# 612_jetracer_esp32s3_030007.net
KiCad netlist of a schematic drawn in EAGLE
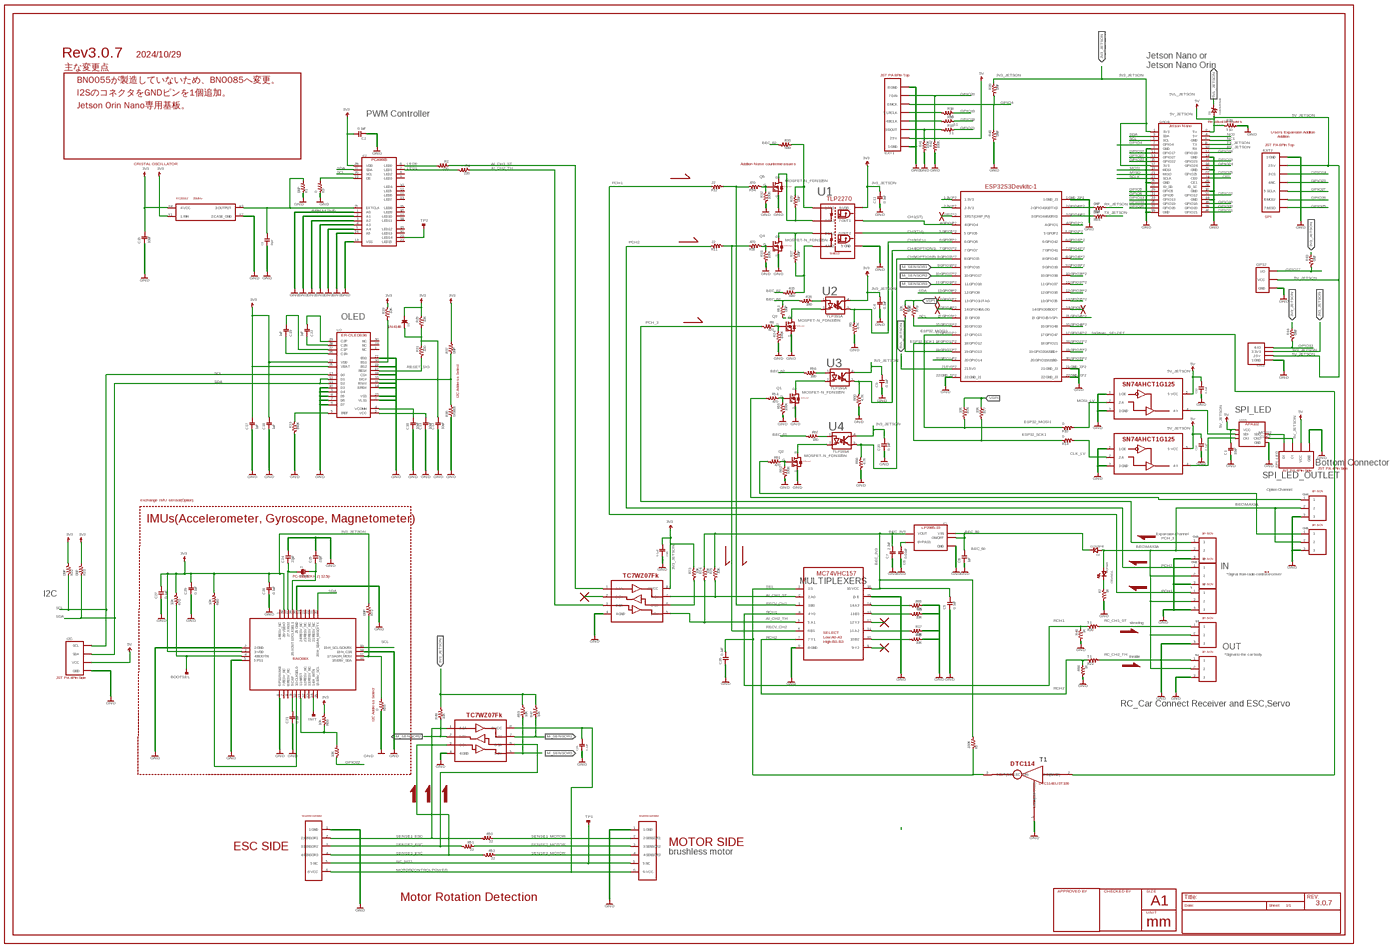
[diagram p0: schematic, sheet 1, overview]
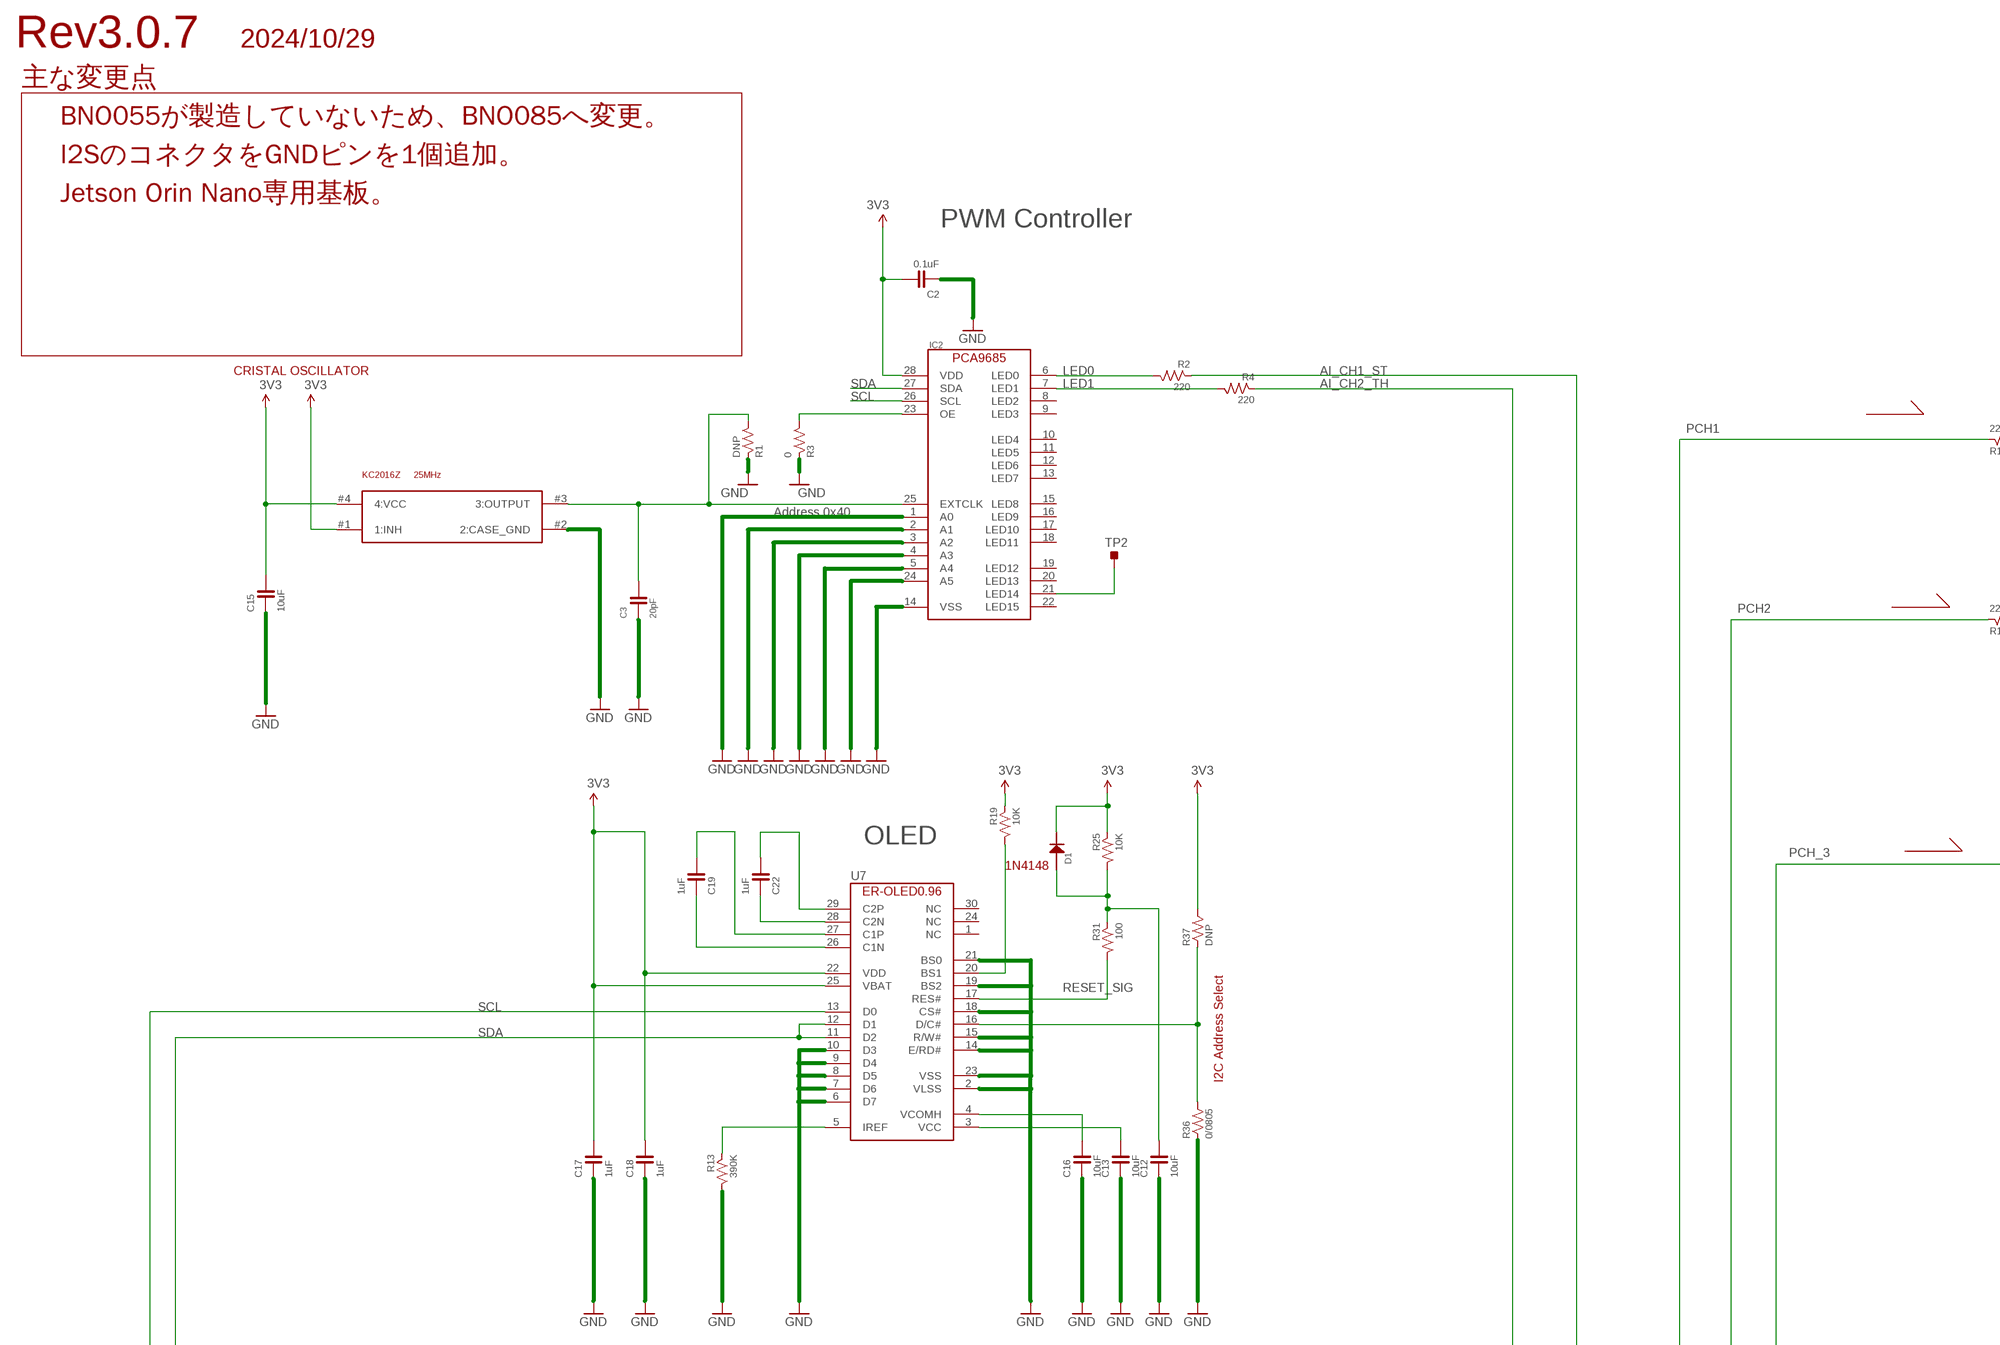
[diagram p1: schematic, sheet 1, part 1 of 4]
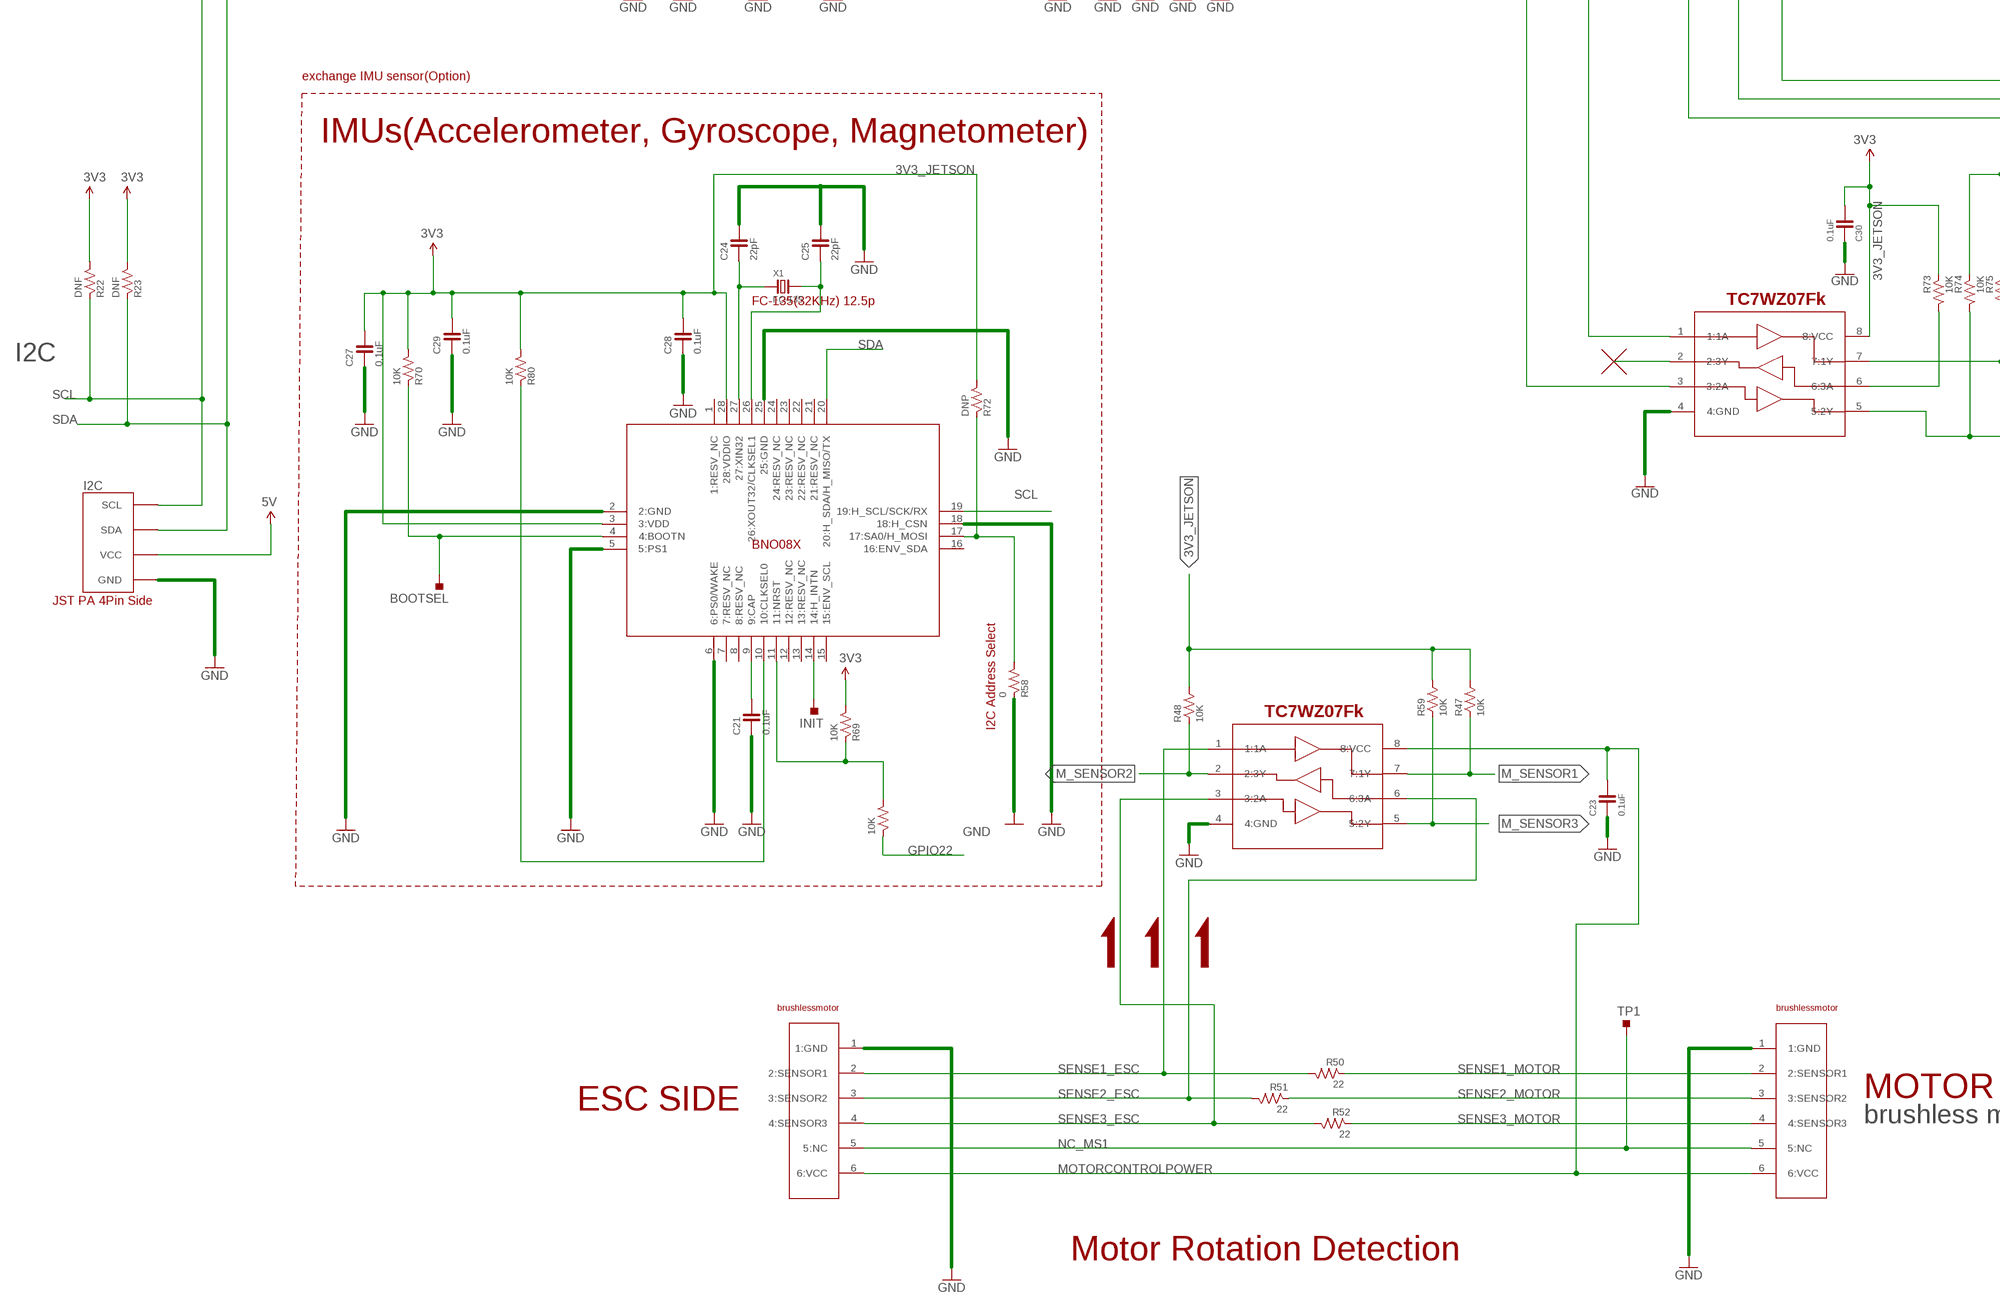
[diagram p2: schematic, sheet 1, part 2 of 4]
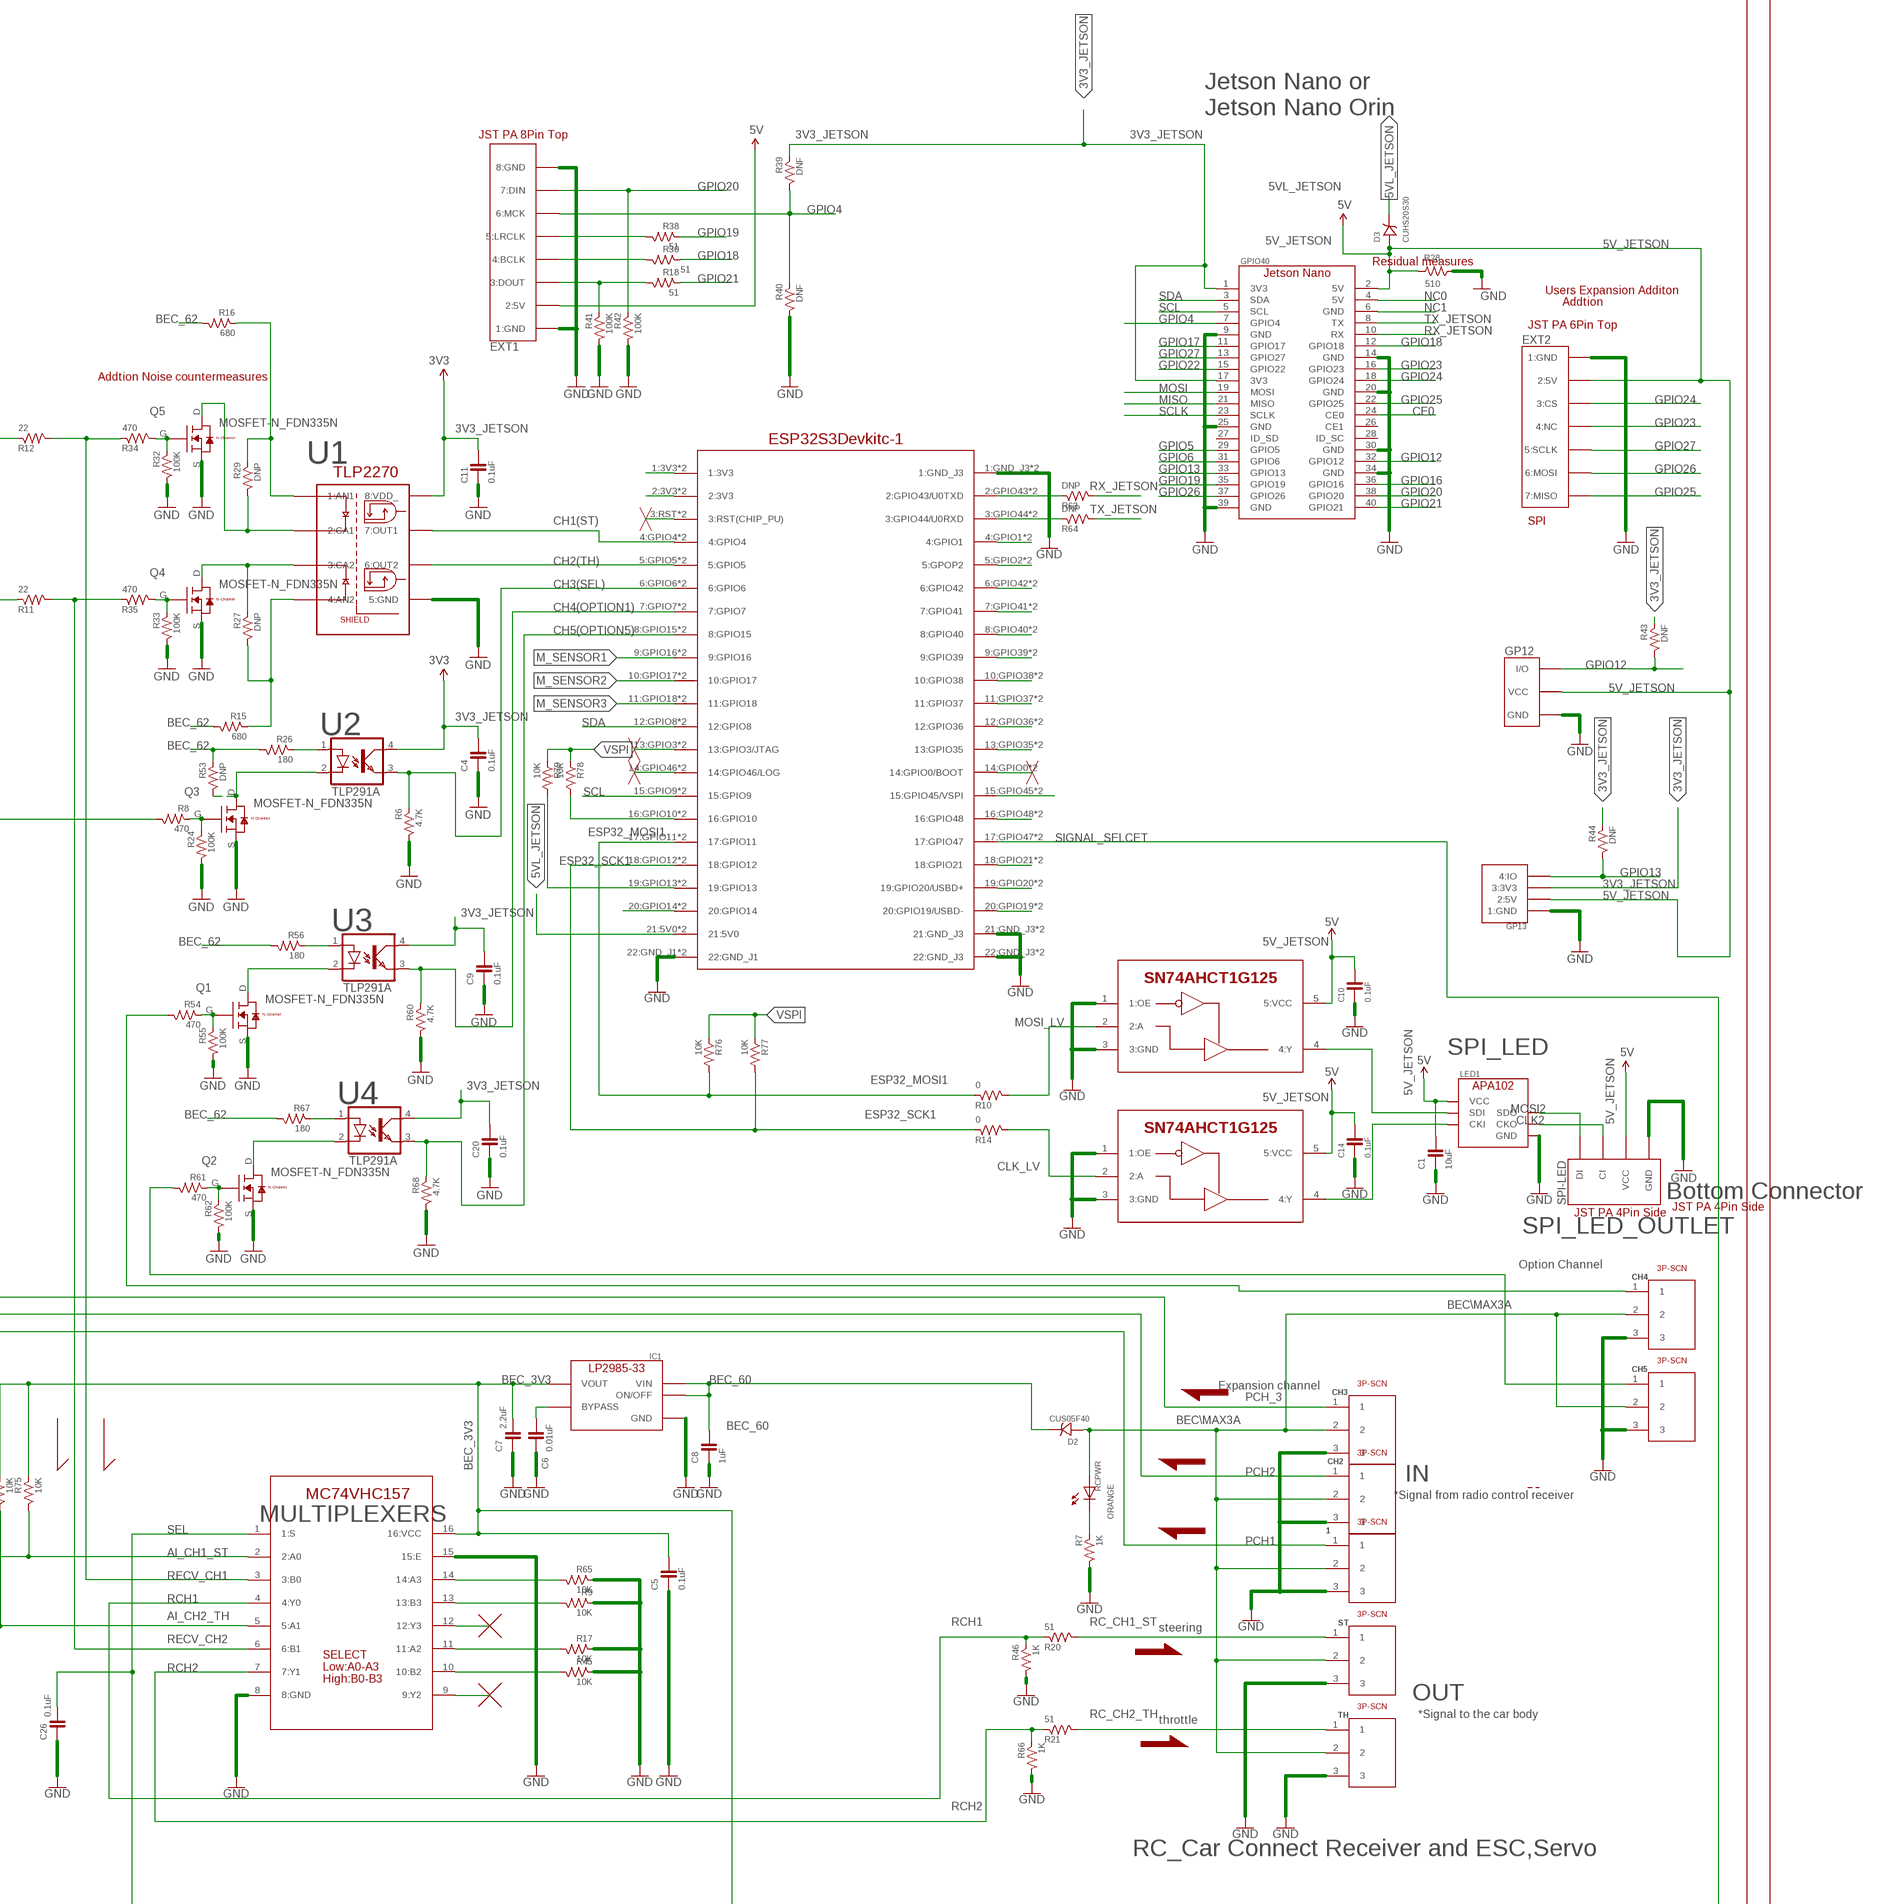
[diagram p3: schematic, sheet 1, part 3 of 4]
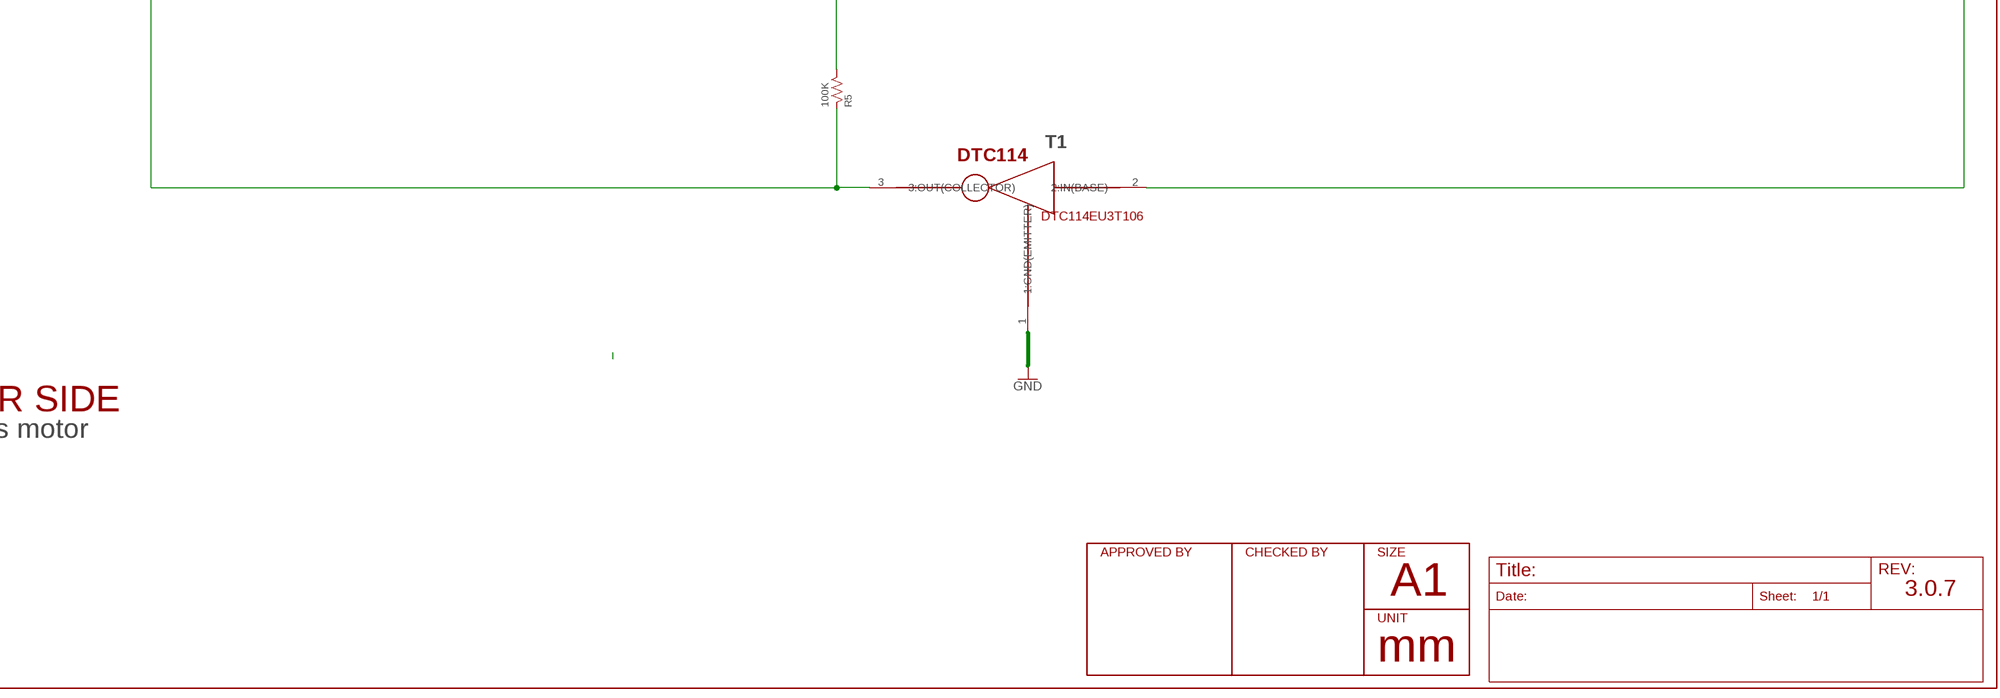
[diagram p4: schematic, sheet 1, part 4 of 4]

(export (version "E")
  (design (tool "Eeschema 10.0.6"))
  (components
    (comp (ref "1")
      (value "3P-SCN")
      (footprint "eagle-import:3P-SCN")
      (libsource (lib "eagle-import") (part "3P-SCN"))
    )
    (comp (ref "BOOTSEL")
      (value "TESTPOINT_TPS-SMD-10SN")
      (footprint "eagle-import:TESTPOINT_SMD-10SN")
      (libsource (lib "eagle-import") (part "TESTPOINT_TPS-SMD-10SN"))
    )
    (comp (ref "C1")
      (value "10uF")
      (footprint "eagle-import:0603")
      (libsource (lib "eagle-import") (part "CAPACITOR-0603"))
    )
    (comp (ref "C2")
      (value "0.1uF")
      (footprint "eagle-import:0603")
      (libsource (lib "eagle-import") (part "CAPACITOR-0603"))
    )
    (comp (ref "C3")
      (value "20pF")
      (footprint "eagle-import:0402")
      (libsource (lib "eagle-import") (part "CAPACITOR-0402"))
    )
    (comp (ref "C4")
      (value "0.1uF")
      (footprint "eagle-import:0603")
      (libsource (lib "eagle-import") (part "CAPACITOR-0603"))
    )
    (comp (ref "C5")
      (value "0.1uF")
      (footprint "eagle-import:0603")
      (fields (field (name "SPICEPREFIX") "C"))
      (libsource (lib "eagle-import") (part "CAPACITOR-0603"))
    )
    (comp (ref "C6")
      (value "0.01uF")
      (footprint "eagle-import:0603")
      (libsource (lib "eagle-import") (part "CAPACITOR-0603"))
    )
    (comp (ref "C7")
      (value "2.2uF")
      (footprint "eagle-import:0603")
      (libsource (lib "eagle-import") (part "CAPACITOR-0603"))
    )
    (comp (ref "C8")
      (value "1uF")
      (footprint "eagle-import:0603")
      (libsource (lib "eagle-import") (part "CAPACITOR-0603"))
    )
    (comp (ref "C9")
      (value "0.1uF")
      (footprint "eagle-import:0603")
      (libsource (lib "eagle-import") (part "CAPACITOR-0603"))
    )
    (comp (ref "C10")
      (value "0.1uF")
      (footprint "eagle-import:0402")
      (libsource (lib "eagle-import") (part "CAPACITOR-0402"))
    )
    (comp (ref "C11")
      (value "0.1uF")
      (footprint "eagle-import:0603")
      (libsource (lib "eagle-import") (part "CAPACITOR-0603"))
    )
    (comp (ref "C12")
      (value "10uF")
      (footprint "eagle-import:0603")
      (libsource (lib "eagle-import") (part "CAPACITOR-0603"))
    )
    (comp (ref "C13")
      (value "10uF")
      (footprint "eagle-import:0603")
      (libsource (lib "eagle-import") (part "CAPACITOR-0603"))
    )
    (comp (ref "C14")
      (value "0.1uF")
      (footprint "eagle-import:0402")
      (libsource (lib "eagle-import") (part "CAPACITOR-0402"))
    )
    (comp (ref "C15")
      (value "10uF")
      (footprint "eagle-import:0603")
      (libsource (lib "eagle-import") (part "CAPACITOR-0603"))
    )
    (comp (ref "C16")
      (value "10uF")
      (footprint "eagle-import:0603")
      (libsource (lib "eagle-import") (part "CAPACITOR-0603"))
    )
    (comp (ref "C17")
      (value "1uF")
      (footprint "eagle-import:0603")
      (libsource (lib "eagle-import") (part "CAPACITOR-0603"))
    )
    (comp (ref "C18")
      (value "1uF")
      (footprint "eagle-import:0603")
      (libsource (lib "eagle-import") (part "CAPACITOR-0603"))
    )
    (comp (ref "C19")
      (value "1uF")
      (footprint "eagle-import:0603")
      (libsource (lib "eagle-import") (part "CAPACITOR-0603"))
    )
    (comp (ref "C20")
      (value "0.1uF")
      (footprint "eagle-import:0603")
      (libsource (lib "eagle-import") (part "CAPACITOR-0603"))
    )
    (comp (ref "C21")
      (value "0.1uF")
      (footprint "eagle-import:0402")
      (libsource (lib "eagle-import") (part "CAPACITOR-0402"))
    )
    (comp (ref "C22")
      (value "1uF")
      (footprint "eagle-import:0603")
      (libsource (lib "eagle-import") (part "CAPACITOR-0603"))
    )
    (comp (ref "C23")
      (value "0.1uF")
      (footprint "eagle-import:0402")
      (libsource (lib "eagle-import") (part "CAPACITOR-0402"))
    )
    (comp (ref "C24")
      (value "22pF")
      (footprint "eagle-import:0402")
      (libsource (lib "eagle-import") (part "CAPACITOR-0402"))
    )
    (comp (ref "C25")
      (value "22pF")
      (footprint "eagle-import:0402")
      (libsource (lib "eagle-import") (part "CAPACITOR-0402"))
    )
    (comp (ref "C26")
      (value "0.1uF")
      (footprint "eagle-import:0603")
      (libsource (lib "eagle-import") (part "CAPACITOR-0603"))
    )
    (comp (ref "C27")
      (value "0.1uF")
      (footprint "eagle-import:0402")
      (libsource (lib "eagle-import") (part "CAPACITOR-0402"))
    )
    (comp (ref "C28")
      (value "0.1uF")
      (footprint "eagle-import:0402")
      (libsource (lib "eagle-import") (part "CAPACITOR-0402"))
    )
    (comp (ref "C29")
      (value "0.1uF")
      (footprint "eagle-import:0402")
      (libsource (lib "eagle-import") (part "CAPACITOR-0402"))
    )
    (comp (ref "C30")
      (value "0.1uF")
      (footprint "eagle-import:0402")
      (libsource (lib "eagle-import") (part "CAPACITOR-0402"))
    )
    (comp (ref "CH2")
      (value "3P-SCN")
      (footprint "eagle-import:3P-SCN")
      (libsource (lib "eagle-import") (part "3P-SCN"))
    )
    (comp (ref "CH3")
      (value "3P-SCN")
      (footprint "eagle-import:3P-SCN")
      (libsource (lib "eagle-import") (part "3P-SCN"))
    )
    (comp (ref "CH4")
      (value "3P-SCN")
      (footprint "eagle-import:3P-SCN")
      (libsource (lib "eagle-import") (part "3P-SCN"))
    )
    (comp (ref "CH5")
      (value "3P-SCN")
      (footprint "eagle-import:3P-SCN")
      (libsource (lib "eagle-import") (part "3P-SCN"))
    )
    (comp (ref "D1")
      (value "1N4148")
      (footprint "eagle-import:1N4148W")
      (libsource (lib "eagle-import") (part "1N4148"))
    )
    (comp (ref "D2")
      (value "CUS05F40")
      (footprint "eagle-import:CUS05F40")
      (libsource (lib "eagle-import") (part "CUS05F40"))
    )
    (comp (ref "D3")
      (value "CUHS20S30")
      (footprint "eagle-import:US2H")
      (libsource (lib "eagle-import") (part "CUHS20S30"))
    )
    (comp (ref "ESC_CON")
      (value "BRUSHLESSMOTOR_CON")
      (footprint "eagle-import:B6B-ZR")
      (libsource (lib "eagle-import") (part "BRUSHLESSMOTOR_CON"))
    )
    (comp (ref "EXT1")
      (value "FABO-I2S-2")
      (footprint "eagle-import:I2S-B08B-PASK-1")
      (libsource (lib "eagle-import") (part "FABO-I2S-2"))
    )
    (comp (ref "EXT2")
      (value "FABO-SPI-7PIN")
      (footprint "eagle-import:SPI-B07B-PASK-1")
      (libsource (lib "eagle-import") (part "FABO-SPI-7PIN"))
    )
    (comp (ref "GP12")
      (value "FABO_BRICK_3PIN-B03B-PASK-1")
      (footprint "eagle-import:FABO_BRICK_3PIN_B03B-PASK-1")
      (libsource (lib "eagle-import") (part "FABO_BRICK_3PIN-B03B-PASK-1"))
    )
    (comp (ref "GP13")
      (value "FABO-GPIO-2G")
      (footprint "eagle-import:GPIO-B04B-PASK-1")
      (libsource (lib "eagle-import") (part "FABO-GPIO-2G"))
    )
    (comp (ref "GPIO40")
      (value "JETSON_NANOJETSON_NANO_OVERALL")
      (footprint "eagle-import:JETSON_NANO_DEMENTION")
      (libsource (lib "eagle-import") (part "JETSON_NANOJETSON_NANO_OVERALL"))
    )
    (comp (ref "I2C")
      (value "FABO-I2C")
      (footprint "eagle-import:I2C-SM04B-PASS-1-FL")
      (libsource (lib "eagle-import") (part "FABO-I2C"))
    )
    (comp (ref "IC1")
      (value "LP2985-33DBVR")
      (footprint "eagle-import:SOT-23-5")
      (libsource (lib "eagle-import") (part "LP2985-33DBVR"))
    )
    (comp (ref "IC2")
      (value "PCA9685PW,BS")
      (footprint "eagle-import:PCA9685")
      (libsource (lib "eagle-import") (part "PCA9685PW,BS"))
    )
    (comp (ref "INIT")
      (value "TESTPOINT_TPS-SMD-10SN")
      (footprint "eagle-import:TESTPOINT_SMD-10SN")
      (libsource (lib "eagle-import") (part "TESTPOINT_TPS-SMD-10SN"))
    )
    (comp (ref "LED1")
      (value "APA102_IPIXEL")
      (footprint "eagle-import:APA102_2020")
      (libsource (lib "eagle-import") (part "APA102_IPIXEL"))
    )
    (comp (ref "MOTOR")
      (value "BRUSHLESSMOTOR_CON")
      (footprint "eagle-import:B6B-ZR")
      (libsource (lib "eagle-import") (part "BRUSHLESSMOTOR_CON"))
    )
    (comp (ref "Q1")
      (value "MOSFET-N_FDN335N")
      (footprint "eagle-import:SUPERSOT-3")
      (libsource (lib "eagle-import") (part "MOSFET-N_FDN335N"))
    )
    (comp (ref "Q2")
      (value "MOSFET-N_FDN335N")
      (footprint "eagle-import:SUPERSOT-3")
      (libsource (lib "eagle-import") (part "MOSFET-N_FDN335N"))
    )
    (comp (ref "Q3")
      (value "MOSFET-N_FDN335N")
      (footprint "eagle-import:SUPERSOT-3")
      (libsource (lib "eagle-import") (part "MOSFET-N_FDN335N"))
    )
    (comp (ref "Q4")
      (value "MOSFET-N_FDN335N")
      (footprint "eagle-import:SUPERSOT-3")
      (libsource (lib "eagle-import") (part "MOSFET-N_FDN335N"))
    )
    (comp (ref "Q5")
      (value "MOSFET-N_FDN335N")
      (footprint "eagle-import:SUPERSOT-3")
      (libsource (lib "eagle-import") (part "MOSFET-N_FDN335N"))
    )
    (comp (ref "R1")
      (value "DNP")
      (footprint "eagle-import:0603")
      (libsource (lib "eagle-import") (part "RESISTOR-0603"))
    )
    (comp (ref "R2")
      (value "220")
      (footprint "eagle-import:0402")
      (fields (field (name "SPICEPREFIX") "R"))
      (libsource (lib "eagle-import") (part "RESISTOR-0402"))
    )
    (comp (ref "R3")
      (value "0")
      (footprint "eagle-import:0603")
      (libsource (lib "eagle-import") (part "RESISTOR-0603"))
    )
    (comp (ref "R4")
      (value "220")
      (footprint "eagle-import:0402")
      (fields (field (name "SPICEPREFIX") "R"))
      (libsource (lib "eagle-import") (part "RESISTOR-0402"))
    )
    (comp (ref "R5")
      (value "100K")
      (footprint "eagle-import:0603")
      (libsource (lib "eagle-import") (part "RESISTOR-0603"))
    )
    (comp (ref "R6")
      (value "4.7K")
      (footprint "eagle-import:0603")
      (libsource (lib "eagle-import") (part "RESISTOR-0603"))
    )
    (comp (ref "R7")
      (value "1K")
      (footprint "eagle-import:0402")
      (fields (field (name "SPICEPREFIX") "R"))
      (libsource (lib "eagle-import") (part "RESISTOR-0402"))
    )
    (comp (ref "R8")
      (value "470")
      (footprint "eagle-import:0603")
      (libsource (lib "eagle-import") (part "RESISTOR-0603"))
    )
    (comp (ref "R9")
      (value "10K")
      (footprint "eagle-import:0402")
      (fields (field (name "SPICEPREFIX") "R"))
      (libsource (lib "eagle-import") (part "RESISTOR-0402"))
    )
    (comp (ref "R10")
      (value "0")
      (footprint "eagle-import:0603")
      (libsource (lib "eagle-import") (part "RESISTOR-0603"))
    )
    (comp (ref "R11")
      (value "22")
      (footprint "eagle-import:0603")
      (libsource (lib "eagle-import") (part "RESISTOR-0603"))
    )
    (comp (ref "R12")
      (value "22")
      (footprint "eagle-import:0603")
      (libsource (lib "eagle-import") (part "RESISTOR-0603"))
    )
    (comp (ref "R13")
      (value "390K")
      (footprint "eagle-import:0603")
      (libsource (lib "eagle-import") (part "RESISTOR-0603"))
    )
    (comp (ref "R14")
      (value "0")
      (footprint "eagle-import:0603")
      (libsource (lib "eagle-import") (part "RESISTOR-0603"))
    )
    (comp (ref "R15")
      (value "680")
      (footprint "eagle-import:0603")
      (libsource (lib "eagle-import") (part "RESISTOR-0603"))
    )
    (comp (ref "R16")
      (value "680")
      (footprint "eagle-import:0603")
      (libsource (lib "eagle-import") (part "RESISTOR-0603"))
    )
    (comp (ref "R17")
      (value "10K")
      (footprint "eagle-import:0402")
      (fields (field (name "SPICEPREFIX") "R"))
      (libsource (lib "eagle-import") (part "RESISTOR-0402"))
    )
    (comp (ref "R18")
      (value "51")
      (footprint "eagle-import:0603")
      (libsource (lib "eagle-import") (part "RESISTOR-0603"))
    )
    (comp (ref "R19")
      (value "10K")
      (footprint "eagle-import:0603")
      (libsource (lib "eagle-import") (part "RESISTOR-0603"))
    )
    (comp (ref "R20")
      (value "51")
      (footprint "eagle-import:0603")
      (libsource (lib "eagle-import") (part "RESISTOR-0603"))
    )
    (comp (ref "R21")
      (value "51")
      (footprint "eagle-import:0603")
      (libsource (lib "eagle-import") (part "RESISTOR-0603"))
    )
    (comp (ref "R22")
      (value "DNF")
      (footprint "eagle-import:0603")
      (libsource (lib "eagle-import") (part "RESISTOR-0603"))
    )
    (comp (ref "R23")
      (value "DNF")
      (footprint "eagle-import:0603")
      (libsource (lib "eagle-import") (part "RESISTOR-0603"))
    )
    (comp (ref "R24")
      (value "100K")
      (footprint "eagle-import:0603")
      (libsource (lib "eagle-import") (part "RESISTOR-0603"))
    )
    (comp (ref "R25")
      (value "10K")
      (footprint "eagle-import:0603")
      (libsource (lib "eagle-import") (part "RESISTOR-0603"))
    )
    (comp (ref "R26")
      (value "180")
      (footprint "eagle-import:0603")
      (libsource (lib "eagle-import") (part "RESISTOR-0603"))
    )
    (comp (ref "R27")
      (value "DNP")
      (footprint "eagle-import:0603")
      (libsource (lib "eagle-import") (part "RESISTOR-0603"))
    )
    (comp (ref "R28")
      (value "510")
      (footprint "eagle-import:0805")
      (libsource (lib "eagle-import") (part "RESISTOR-0805"))
    )
    (comp (ref "R29")
      (value "DNP")
      (footprint "eagle-import:0603")
      (libsource (lib "eagle-import") (part "RESISTOR-0603"))
    )
    (comp (ref "R30")
      (value "51")
      (footprint "eagle-import:0603")
      (libsource (lib "eagle-import") (part "RESISTOR-0603"))
    )
    (comp (ref "R31")
      (value "100")
      (footprint "eagle-import:0603")
      (libsource (lib "eagle-import") (part "RESISTOR-0603"))
    )
    (comp (ref "R32")
      (value "100K")
      (footprint "eagle-import:0603")
      (libsource (lib "eagle-import") (part "RESISTOR-0603"))
    )
    (comp (ref "R33")
      (value "100K")
      (footprint "eagle-import:0603")
      (libsource (lib "eagle-import") (part "RESISTOR-0603"))
    )
    (comp (ref "R34")
      (value "470")
      (footprint "eagle-import:0603")
      (libsource (lib "eagle-import") (part "RESISTOR-0603"))
    )
    (comp (ref "R35")
      (value "470")
      (footprint "eagle-import:0603")
      (libsource (lib "eagle-import") (part "RESISTOR-0603"))
    )
    (comp (ref "R36")
      (value "0/0805")
      (footprint "eagle-import:0805")
      (libsource (lib "eagle-import") (part "RESISTOR-0805"))
    )
    (comp (ref "R37")
      (value "DNP")
      (footprint "eagle-import:0805")
      (fields (field (name "SPICEPREFIX") "R"))
      (libsource (lib "eagle-import") (part "RESISTOR-0805"))
    )
    (comp (ref "R38")
      (value "51")
      (footprint "eagle-import:0603")
      (libsource (lib "eagle-import") (part "RESISTOR-0603"))
    )
    (comp (ref "R39")
      (value "DNF")
      (footprint "eagle-import:0603")
      (libsource (lib "eagle-import") (part "RESISTOR-0603"))
    )
    (comp (ref "R40")
      (value "DNF")
      (footprint "eagle-import:0603")
      (libsource (lib "eagle-import") (part "RESISTOR-0603"))
    )
    (comp (ref "R41")
      (value "100K")
      (footprint "eagle-import:0603")
      (libsource (lib "eagle-import") (part "RESISTOR-0603"))
    )
    (comp (ref "R42")
      (value "100K")
      (footprint "eagle-import:0603")
      (libsource (lib "eagle-import") (part "RESISTOR-0603"))
    )
    (comp (ref "R43")
      (value "DNF")
      (footprint "eagle-import:0603")
      (libsource (lib "eagle-import") (part "RESISTOR-0603"))
    )
    (comp (ref "R44")
      (value "DNF")
      (footprint "eagle-import:0603")
      (libsource (lib "eagle-import") (part "RESISTOR-0603"))
    )
    (comp (ref "R45")
      (value "10K")
      (footprint "eagle-import:0402")
      (fields (field (name "SPICEPREFIX") "R"))
      (libsource (lib "eagle-import") (part "RESISTOR-0402"))
    )
    (comp (ref "R46")
      (value "1K")
      (footprint "eagle-import:0402")
      (fields (field (name "SPICEPREFIX") "R"))
      (libsource (lib "eagle-import") (part "RESISTOR-0402"))
    )
    (comp (ref "R47")
      (value "10K")
      (footprint "eagle-import:0402")
      (libsource (lib "eagle-import") (part "RESISTOR-0402"))
    )
    (comp (ref "R48")
      (value "10K")
      (footprint "eagle-import:0402")
      (libsource (lib "eagle-import") (part "RESISTOR-0402"))
    )
    (comp (ref "R50")
      (value "22")
      (footprint "eagle-import:0603")
      (libsource (lib "eagle-import") (part "RESISTOR-0603"))
    )
    (comp (ref "R51")
      (value "22")
      (footprint "eagle-import:0603")
      (libsource (lib "eagle-import") (part "RESISTOR-0603"))
    )
    (comp (ref "R52")
      (value "22")
      (footprint "eagle-import:0603")
      (libsource (lib "eagle-import") (part "RESISTOR-0603"))
    )
    (comp (ref "R53")
      (value "DNP")
      (footprint "eagle-import:0603")
      (libsource (lib "eagle-import") (part "RESISTOR-0603"))
    )
    (comp (ref "R54")
      (value "470")
      (footprint "eagle-import:0603")
      (libsource (lib "eagle-import") (part "RESISTOR-0603"))
    )
    (comp (ref "R55")
      (value "100K")
      (footprint "eagle-import:0603")
      (libsource (lib "eagle-import") (part "RESISTOR-0603"))
    )
    (comp (ref "R56")
      (value "180")
      (footprint "eagle-import:0603")
      (libsource (lib "eagle-import") (part "RESISTOR-0603"))
    )
    (comp (ref "R58")
      (value "0")
      (footprint "eagle-import:0402")
      (libsource (lib "eagle-import") (part "RESISTOR-0402"))
    )
    (comp (ref "R59")
      (value "10K")
      (footprint "eagle-import:0402")
      (libsource (lib "eagle-import") (part "RESISTOR-0402"))
    )
    (comp (ref "R60")
      (value "4.7K")
      (footprint "eagle-import:0603")
      (libsource (lib "eagle-import") (part "RESISTOR-0603"))
    )
    (comp (ref "R61")
      (value "470")
      (footprint "eagle-import:0603")
      (libsource (lib "eagle-import") (part "RESISTOR-0603"))
    )
    (comp (ref "R62")
      (value "100K")
      (footprint "eagle-import:0603")
      (libsource (lib "eagle-import") (part "RESISTOR-0603"))
    )
    (comp (ref "R63")
      (value "DNP")
      (footprint "eagle-import:0603")
      (libsource (lib "eagle-import") (part "RESISTOR-0603"))
    )
    (comp (ref "R64")
      (value "DNP")
      (footprint "eagle-import:0603")
      (libsource (lib "eagle-import") (part "RESISTOR-0603"))
    )
    (comp (ref "R65")
      (value "10K")
      (footprint "eagle-import:0402")
      (fields (field (name "SPICEPREFIX") "R"))
      (libsource (lib "eagle-import") (part "RESISTOR-0402"))
    )
    (comp (ref "R66")
      (value "1K")
      (footprint "eagle-import:0402")
      (fields (field (name "SPICEPREFIX") "R"))
      (libsource (lib "eagle-import") (part "RESISTOR-0402"))
    )
    (comp (ref "R67")
      (value "180")
      (footprint "eagle-import:0603")
      (libsource (lib "eagle-import") (part "RESISTOR-0603"))
    )
    (comp (ref "R68")
      (value "4.7K")
      (footprint "eagle-import:0603")
      (libsource (lib "eagle-import") (part "RESISTOR-0603"))
    )
    (comp (ref "R69")
      (value "10K")
      (footprint "eagle-import:0402")
      (libsource (lib "eagle-import") (part "RESISTOR-0402"))
    )
    (comp (ref "R70")
      (value "10K")
      (footprint "eagle-import:0402")
      (libsource (lib "eagle-import") (part "RESISTOR-0402"))
    )
    (comp (ref "R71")
      (value "10K")
      (footprint "eagle-import:0402")
      (libsource (lib "eagle-import") (part "RESISTOR-0402"))
    )
    (comp (ref "R72")
      (value "DNP")
      (footprint "eagle-import:0402")
      (fields (field (name "SPICEPREFIX") "R"))
      (libsource (lib "eagle-import") (part "RESISTOR-0402"))
    )
    (comp (ref "R73")
      (value "10K")
      (footprint "eagle-import:0402")
      (fields (field (name "SPICEPREFIX") "R"))
      (libsource (lib "eagle-import") (part "RESISTOR-0402"))
    )
    (comp (ref "R74")
      (value "10K")
      (footprint "eagle-import:0402")
      (fields (field (name "SPICEPREFIX") "R"))
      (libsource (lib "eagle-import") (part "RESISTOR-0402"))
    )
    (comp (ref "R75")
      (value "10K")
      (footprint "eagle-import:0402")
      (fields (field (name "SPICEPREFIX") "R"))
      (libsource (lib "eagle-import") (part "RESISTOR-0402"))
    )
    (comp (ref "R76")
      (value "10K")
      (footprint "eagle-import:0402")
      (fields (field (name "SPICEPREFIX") "R"))
      (libsource (lib "eagle-import") (part "RESISTOR-0402"))
    )
    (comp (ref "R77")
      (value "10K")
      (footprint "eagle-import:0402")
      (fields (field (name "SPICEPREFIX") "R"))
      (libsource (lib "eagle-import") (part "RESISTOR-0402"))
    )
    (comp (ref "R78")
      (value "10K")
      (footprint "eagle-import:0402")
      (fields (field (name "SPICEPREFIX") "R"))
      (libsource (lib "eagle-import") (part "RESISTOR-0402"))
    )
    (comp (ref "R79")
      (value "10K")
      (footprint "eagle-import:0402")
      (fields (field (name "SPICEPREFIX") "R"))
      (libsource (lib "eagle-import") (part "RESISTOR-0402"))
    )
    (comp (ref "R80")
      (value "10K")
      (footprint "eagle-import:0402")
      (libsource (lib "eagle-import") (part "RESISTOR-0402"))
    )
    (comp (ref "RCPWR")
      (value "ORANGE")
      (footprint "eagle-import:0603")
      (libsource (lib "eagle-import") (part "LED-0603"))
    )
    (comp (ref "SPI-LED")
      (value "FABO-SPI-LED")
      (footprint "eagle-import:SPI-SM04B-PASS-1-FL")
      (libsource (lib "eagle-import") (part "FABO-SPI-LED"))
    )
    (comp (ref "ST")
      (value "3P-SCN")
      (footprint "eagle-import:3P-SCN")
      (libsource (lib "eagle-import") (part "3P-SCN"))
    )
    (comp (ref "T1")
      (value "DTC114EU3")
      (footprint "eagle-import:SOT-323FL_SC-85(UMT3F)")
      (libsource (lib "eagle-import") (part "DTC114EU3"))
    )
    (comp (ref "TH")
      (value "3P-SCN")
      (footprint "eagle-import:3P-SCN")
      (libsource (lib "eagle-import") (part "3P-SCN"))
    )
    (comp (ref "TP1")
      (value "TESTPOINT_TPS-SMD-10SN")
      (footprint "eagle-import:TESTPOINT_SMD-10SN")
      (libsource (lib "eagle-import") (part "TESTPOINT_TPS-SMD-10SN"))
    )
    (comp (ref "TP2")
      (value "TESTPOINT_TPS-SMD-10SN")
      (footprint "eagle-import:TESTPOINT_SMD-10SN")
      (libsource (lib "eagle-import") (part "TESTPOINT_TPS-SMD-10SN"))
    )
    (comp (ref "U$1")
      (value "MC74VHC157")
      (footprint "eagle-import:MC74VHC157_TSSOP-16")
      (libsource (lib "eagle-import") (part "MC74VHC157"))
    )
    (comp (ref "U$3")
      (value "TC7WZ07FK")
      (footprint "eagle-import:SOT-765")
      (libsource (lib "eagle-import") (part "TC7WZ07FK"))
    )
    (comp (ref "U$5")
      (value "TC7WZ07FK")
      (footprint "eagle-import:SOT-765")
      (libsource (lib "eagle-import") (part "TC7WZ07FK"))
    )
    (comp (ref "U$9")
      (value "SN74AHCT1G125")
      (footprint "eagle-import:SOT-1DOT1")
      (libsource (lib "eagle-import") (part "SN74AHCT1G125"))
    )
    (comp (ref "U$10")
      (value "SN74AHCT1G125")
      (footprint "eagle-import:SOT-1DOT1")
      (libsource (lib "eagle-import") (part "SN74AHCT1G125"))
    )
    (comp (ref "U$11")
      (value "KC2016Z")
      (footprint "eagle-import:KC2016Z")
      (libsource (lib "eagle-import") (part "KC2016Z"))
    )
    (comp (ref "U$14")
      (value "ESP32S3DEVKITC-1-DUAL")
      (footprint "eagle-import:ESP32S3DEVKITC-1-DUAL")
      (libsource (lib "eagle-import") (part "ESP32S3DEVKITC-1-DUAL"))
    )
    (comp (ref "U1")
      (value "TLP2270")
      (footprint "eagle-import:TLP2270")
      (libsource (lib "eagle-import") (part "TLP2270"))
    )
    (comp (ref "U2")
      (value "TLP291A")
      (footprint "eagle-import:11-3C1")
      (libsource (lib "eagle-import") (part "TLP291A"))
    )
    (comp (ref "U3")
      (value "TLP291A")
      (footprint "eagle-import:11-3C1")
      (libsource (lib "eagle-import") (part "TLP291A"))
    )
    (comp (ref "U4")
      (value "TLP291A")
      (footprint "eagle-import:11-3C1")
      (libsource (lib "eagle-import") (part "TLP291A"))
    )
    (comp (ref "U6")
      (value "BNO085")
      (footprint "eagle-import:BNO08X(LGA)")
      (libsource (lib "eagle-import") (part "BNO085"))
    )
    (comp (ref "U7")
      (value "ER-OLED0.96-1ER-CON30HT-1")
      (footprint "eagle-import:ER-CON30HT-1")
      (libsource (lib "eagle-import") (part "ER-OLED0.96-1ER-CON30HT-1"))
    )
    (comp (ref "X1")
      (value "FC-135")
      (footprint "eagle-import:FC-135")
      (libsource (lib "eagle-import") (part "FC-135"))
    )
  )
  (nets
    (net (code "1") (name "/AI_CH1_ST") (class "Default")
      (node (ref "R2") (pin "1") (pinfunction "1_1") (pintype "bidirectional"))
      (node (ref "U$5") (pin "1") (pinfunction "1:1A_1") (pintype "input"))
    )
    (net (code "2") (name "/AI_CH2_TH") (class "Default")
      (node (ref "R4") (pin "1") (pinfunction "1_1") (pintype "bidirectional"))
      (node (ref "U$5") (pin "3") (pinfunction "3:2A_3") (pintype "input"))
    )
    (net (code "3") (name "/BEC\\MAX3A") (class "Default")
      (node (ref "1") (pin "2") (pinfunction "2_2") (pintype "power_in"))
      (node (ref "CH2") (pin "2") (pinfunction "2_2") (pintype "power_in"))
      (node (ref "CH3") (pin "2") (pinfunction "2_2") (pintype "power_in"))
      (node (ref "CH4") (pin "2") (pinfunction "2_2") (pintype "power_in"))
      (node (ref "CH5") (pin "2") (pinfunction "2_2") (pintype "power_in"))
      (node (ref "D2") (pin "A") (pinfunction "ANODE_A") (pintype "bidirectional"))
      (node (ref "RCPWR") (pin "ANODE") (pinfunction "ANODE_ANODE") (pintype "passive"))
      (node (ref "ST") (pin "2") (pinfunction "2_2") (pintype "power_in"))
      (node (ref "TH") (pin "2") (pinfunction "2_2") (pintype "power_in"))
    )
    (net (code "4") (name "/BEC_3V3") (class "Default")
      (node (ref "C5") (pin "2") (pinfunction "2_2") (pintype "passive"))
      (node (ref "C7") (pin "2") (pinfunction "2_2") (pintype "passive"))
      (node (ref "IC1") (pin "5") (pinfunction "VOUT_5") (pintype "output"))
      (node (ref "R5") (pin "2") (pinfunction "2_2") (pintype "bidirectional"))
      (node (ref "R74") (pin "1") (pinfunction "1_1") (pintype "bidirectional"))
      (node (ref "R75") (pin "1") (pinfunction "1_1") (pintype "bidirectional"))
      (node (ref "U$1") (pin "16") (pinfunction "16:VCC_16") (pintype "bidirectional"))
    )
    (net (code "5") (name "/BEC_60") (class "Default")
      (node (ref "C8") (pin "2") (pinfunction "2_2") (pintype "passive"))
      (node (ref "D2") (pin "C") (pinfunction "CATHODE_C") (pintype "bidirectional"))
      (node (ref "IC1") (pin "1") (pinfunction "VIN_1") (pintype "input"))
      (node (ref "IC1") (pin "3") (pinfunction "ON/OFF_3") (pintype "input"))
    )
    (net (code "6") (name "/BEC_62") (class "Default")
      (node (ref "R15") (pin "2") (pinfunction "2_2") (pintype "bidirectional"))
      (node (ref "R16") (pin "2") (pinfunction "2_2") (pintype "bidirectional"))
      (node (ref "R26") (pin "2") (pinfunction "2_2") (pintype "bidirectional"))
      (node (ref "R53") (pin "1") (pinfunction "1_1") (pintype "bidirectional"))
      (node (ref "R56") (pin "2") (pinfunction "2_2") (pintype "bidirectional"))
      (node (ref "R67") (pin "2") (pinfunction "2_2") (pintype "bidirectional"))
    )
    (net (code "7") (name "/CE0") (class "Default")
      (node (ref "GPIO40") (pin "24") (pinfunction "CE0_24") (pintype "bidirectional"))
    )
    (net (code "8") (name "/CH1(ST)") (class "Default")
      (node (ref "U$14") (pin "4:GPIO4") (pinfunction "4:GPIO4_4:GPIO4") (pintype "bidirectional"))
      (node (ref "U$14") (pin "4:GPIO4_L") (pinfunction "4:GPIO4_4:GPIO4_L") (pintype "bidirectional"))
      (node (ref "U1") (pin "7") (pinfunction "7:OUT1_7") (pintype "bidirectional"))
    )
    (net (code "9") (name "/CH2(TH)") (class "Default")
      (node (ref "U$14") (pin "5:GPIO5") (pinfunction "5:GPIO5_5:GPIO5") (pintype "bidirectional"))
      (node (ref "U$14") (pin "5:GPIO5_L") (pinfunction "5:GPIO5_5:GPIO5_L") (pintype "bidirectional"))
      (node (ref "U1") (pin "6") (pinfunction "6:OUT2_6") (pintype "bidirectional"))
    )
    (net (code "10") (name "/CH3(SEL)") (class "Default")
      (node (ref "R6") (pin "1") (pinfunction "1_1") (pintype "bidirectional"))
      (node (ref "U$14") (pin "6:GPIO6") (pinfunction "6:GPIO6_6:GPIO6") (pintype "bidirectional"))
      (node (ref "U$14") (pin "6:GPIO6_L") (pinfunction "6:GPIO6_6:GPIO6_L") (pintype "bidirectional"))
      (node (ref "U2") (pin "3") (pinfunction "EMI_3") (pintype "passive"))
    )
    (net (code "11") (name "/CH4(OPTION1)") (class "Default")
      (node (ref "R60") (pin "1") (pinfunction "1_1") (pintype "bidirectional"))
      (node (ref "U$14") (pin "7:GPIO7") (pinfunction "7:GPIO7_7:GPIO7") (pintype "bidirectional"))
      (node (ref "U$14") (pin "7:GPIO7_L") (pinfunction "7:GPIO7_7:GPIO7_L") (pintype "bidirectional"))
      (node (ref "U3") (pin "3") (pinfunction "EMI_3") (pintype "passive"))
    )
    (net (code "12") (name "/CH5(OPTION5)") (class "Default")
      (node (ref "R68") (pin "1") (pinfunction "1_1") (pintype "bidirectional"))
      (node (ref "U$14") (pin "8:GPIO15") (pinfunction "8:GPIO15_8:GPIO15") (pintype "bidirectional"))
      (node (ref "U$14") (pin "8:GPIO15_L") (pinfunction "8:GPIO15_8:GPIO15_L") (pintype "bidirectional"))
      (node (ref "U4") (pin "3") (pinfunction "EMI_3") (pintype "passive"))
    )
    (net (code "13") (name "/CLK2") (class "Default")
      (node (ref "LED1") (pin "CKO") (pinfunction "CKO_CKO") (pintype "bidirectional"))
      (node (ref "SPI-LED") (pin "CI") (pinfunction "CI_CI") (pintype "bidirectional"))
    )
    (net (code "14") (name "/CLK_LV") (class "Default")
      (node (ref "R14") (pin "2") (pinfunction "2_2") (pintype "bidirectional"))
      (node (ref "U$10") (pin "2") (pinfunction "2:A_2") (pintype "input"))
    )
    (net (code "15") (name "/ESP32_MOSI1") (class "Default")
      (node (ref "R10") (pin "1") (pinfunction "1_1") (pintype "bidirectional"))
      (node (ref "R76") (pin "2") (pinfunction "2_2") (pintype "bidirectional"))
      (node (ref "U$14") (pin "17:GPIO11") (pinfunction "17:GPIO11_17:GPIO11") (pintype "bidirectional"))
      (node (ref "U$14") (pin "17:GPIO11_L") (pinfunction "17:GPIO11_17:GPIO11_L") (pintype "bidirectional"))
    )
    (net (code "16") (name "/ESP32_SCK1") (class "Default")
      (node (ref "R14") (pin "1") (pinfunction "1_1") (pintype "bidirectional"))
      (node (ref "R77") (pin "2") (pinfunction "2_2") (pintype "bidirectional"))
      (node (ref "U$14") (pin "18:GPIO12") (pinfunction "18:GPIO12_18:GPIO12") (pintype "bidirectional"))
      (node (ref "U$14") (pin "18:GPIO12_L") (pinfunction "18:GPIO12_18:GPIO12_L") (pintype "bidirectional"))
    )
    (net (code "17") (name "/GPIO4") (class "Default")
      (node (ref "EXT1") (pin "6:MCK") (pinfunction "6:MCK_6:MCK") (pintype "output"))
      (node (ref "GPIO40") (pin "7") (pinfunction "GPIO4_7") (pintype "bidirectional"))
      (node (ref "R39") (pin "2") (pinfunction "2_2") (pintype "bidirectional"))
      (node (ref "R40") (pin "1") (pinfunction "1_1") (pintype "bidirectional"))
    )
    (net (code "18") (name "/GPIO5") (class "Default")
      (node (ref "GPIO40") (pin "29") (pinfunction "GPIO5_29") (pintype "bidirectional"))
    )
    (net (code "19") (name "/GPIO6") (class "Default")
      (node (ref "GPIO40") (pin "31") (pinfunction "GPIO6_31") (pintype "bidirectional"))
    )
    (net (code "20") (name "/GPIO12") (class "Default")
      (node (ref "GP12") (pin "I/O") (pinfunction "I/O_I/O") (pintype "bidirectional"))
      (node (ref "GPIO40") (pin "32") (pinfunction "GPIO12_32") (pintype "bidirectional"))
      (node (ref "R43") (pin "2") (pinfunction "2_2") (pintype "bidirectional"))
    )
    (net (code "21") (name "/GPIO13") (class "Default")
      (node (ref "GP13") (pin "IO") (pinfunction "4:IO_IO") (pintype "bidirectional"))
      (node (ref "GPIO40") (pin "33") (pinfunction "GPIO13_33") (pintype "bidirectional"))
      (node (ref "R44") (pin "2") (pinfunction "2_2") (pintype "bidirectional"))
    )
    (net (code "22") (name "/GPIO16") (class "Default")
      (node (ref "GPIO40") (pin "36") (pinfunction "GPIO16_36") (pintype "bidirectional"))
    )
    (net (code "23") (name "/GPIO17") (class "Default")
      (node (ref "GPIO40") (pin "11") (pinfunction "GPIO17_11") (pintype "bidirectional"))
    )
    (net (code "24") (name "/GPIO18") (class "Default")
      (node (ref "GPIO40") (pin "12") (pinfunction "GPIO18_12") (pintype "bidirectional"))
      (node (ref "R30") (pin "1") (pinfunction "1_1") (pintype "bidirectional"))
    )
    (net (code "25") (name "/GPIO19") (class "Default")
      (node (ref "GPIO40") (pin "35") (pinfunction "GPIO19_35") (pintype "bidirectional"))
      (node (ref "R38") (pin "1") (pinfunction "1_1") (pintype "bidirectional"))
    )
    (net (code "26") (name "/GPIO20") (class "Default")
      (node (ref "EXT1") (pin "7:DIN") (pinfunction "7:DIN_7:DIN") (pintype "output"))
      (node (ref "GPIO40") (pin "38") (pinfunction "GPIO20_38") (pintype "bidirectional"))
      (node (ref "R42") (pin "1") (pinfunction "1_1") (pintype "bidirectional"))
    )
    (net (code "27") (name "/GPIO21") (class "Default")
      (node (ref "GPIO40") (pin "40") (pinfunction "GPIO21_40") (pintype "bidirectional"))
      (node (ref "R18") (pin "1") (pinfunction "1_1") (pintype "bidirectional"))
    )
    (net (code "28") (name "/GPIO22") (class "Default")
      (node (ref "GPIO40") (pin "15") (pinfunction "GPIO22_15") (pintype "bidirectional"))
      (node (ref "R71") (pin "1") (pinfunction "1_1") (pintype "bidirectional"))
    )
    (net (code "29") (name "/GPIO23") (class "Default")
      (node (ref "EXT2") (pin "4") (pinfunction "4:NC_4") (pintype "bidirectional"))
      (node (ref "GPIO40") (pin "16") (pinfunction "GPIO23_16") (pintype "bidirectional"))
    )
    (net (code "30") (name "/GPIO24") (class "Default")
      (node (ref "EXT2") (pin "3") (pinfunction "3:CS_3") (pintype "bidirectional"))
      (node (ref "GPIO40") (pin "18") (pinfunction "GPIO24_18") (pintype "bidirectional"))
    )
    (net (code "31") (name "/GPIO25") (class "Default")
      (node (ref "EXT2") (pin "7") (pinfunction "7:MISO_7") (pintype "bidirectional"))
      (node (ref "GPIO40") (pin "22") (pinfunction "GPIO25_22") (pintype "bidirectional"))
    )
    (net (code "32") (name "/GPIO26") (class "Default")
      (node (ref "EXT2") (pin "6") (pinfunction "6:MOSI_6") (pintype "bidirectional"))
      (node (ref "GPIO40") (pin "37") (pinfunction "GPIO26_37") (pintype "bidirectional"))
    )
    (net (code "33") (name "/GPIO27") (class "Default")
      (node (ref "EXT2") (pin "5") (pinfunction "5:SCLK_5") (pintype "bidirectional"))
      (node (ref "GPIO40") (pin "13") (pinfunction "GPIO27_13") (pintype "bidirectional"))
    )
    (net (code "34") (name "/LED0") (class "Default")
      (node (ref "IC2") (pin "6") (pinfunction "LED0_6") (pintype "bidirectional"))
      (node (ref "R2") (pin "2") (pinfunction "2_2") (pintype "bidirectional"))
    )
    (net (code "35") (name "/LED1") (class "Default")
      (node (ref "IC2") (pin "7") (pinfunction "LED1_7") (pintype "bidirectional"))
      (node (ref "R4") (pin "2") (pinfunction "2_2") (pintype "bidirectional"))
    )
    (net (code "36") (name "/MISO") (class "Default")
      (node (ref "GPIO40") (pin "21") (pinfunction "MISO_21") (pintype "bidirectional"))
    )
    (net (code "37") (name "/MOSI") (class "Default")
      (node (ref "GPIO40") (pin "19") (pinfunction "MOSI_19") (pintype "bidirectional"))
    )
    (net (code "38") (name "/MOSI2") (class "Default")
      (node (ref "LED1") (pin "SDO") (pinfunction "SDO_SDO") (pintype "bidirectional"))
      (node (ref "SPI-LED") (pin "DI") (pinfunction "DI_DI") (pintype "bidirectional"))
    )
    (net (code "39") (name "/MOSI_LV") (class "Default")
      (node (ref "R10") (pin "2") (pinfunction "2_2") (pintype "bidirectional"))
      (node (ref "U$9") (pin "2") (pinfunction "2:A_2") (pintype "input"))
    )
    (net (code "40") (name "/MOTORCONTROLPOWER") (class "Default")
      (node (ref "C23") (pin "2") (pinfunction "2_2") (pintype "passive"))
      (node (ref "ESC_CON") (pin "6") (pinfunction "6:VCC_6") (pintype "bidirectional"))
      (node (ref "MOTOR") (pin "6") (pinfunction "6:VCC_6") (pintype "bidirectional"))
      (node (ref "U$3") (pin "8") (pinfunction "8:VCC_8") (pintype "power_in"))
    )
    (net (code "41") (name "/NC0") (class "Default")
      (node (ref "GPIO40") (pin "4") (pinfunction "5V_4") (pintype "bidirectional"))
    )
    (net (code "42") (name "/NC1") (class "Default")
      (node (ref "GPIO40") (pin "6") (pinfunction "GND_6") (pintype "bidirectional"))
    )
    (net (code "43") (name "/NC_MS1") (class "Default")
      (node (ref "ESC_CON") (pin "5") (pinfunction "5:NC_5") (pintype "bidirectional"))
      (node (ref "MOTOR") (pin "5") (pinfunction "5:NC_5") (pintype "bidirectional"))
      (node (ref "TP1") (pin "TP") (pinfunction "TP_TP") (pintype "passive"))
    )
    (net (code "44") (name "/PCH1") (class "Default")
      (node (ref "1") (pin "1") (pinfunction "1_1") (pintype "bidirectional"))
      (node (ref "R12") (pin "1") (pinfunction "1_1") (pintype "bidirectional"))
    )
    (net (code "45") (name "/PCH2") (class "Default")
      (node (ref "CH2") (pin "1") (pinfunction "1_1") (pintype "bidirectional"))
      (node (ref "R11") (pin "1") (pinfunction "1_1") (pintype "bidirectional"))
    )
    (net (code "46") (name "/PCH_3") (class "Default")
      (node (ref "CH3") (pin "1") (pinfunction "1_1") (pintype "bidirectional"))
      (node (ref "R8") (pin "2") (pinfunction "2_2") (pintype "bidirectional"))
    )
    (net (code "47") (name "/RCH1") (class "Default")
      (node (ref "R20") (pin "1") (pinfunction "1_1") (pintype "bidirectional"))
      (node (ref "R46") (pin "1") (pinfunction "1_1") (pintype "bidirectional"))
      (node (ref "U$1") (pin "4") (pinfunction "4:Y0_4") (pintype "bidirectional"))
    )
    (net (code "48") (name "/RCH2") (class "Default")
      (node (ref "R21") (pin "1") (pinfunction "1_1") (pintype "bidirectional"))
      (node (ref "R66") (pin "1") (pinfunction "1_1") (pintype "bidirectional"))
      (node (ref "U$1") (pin "7") (pinfunction "7:Y1_7") (pintype "bidirectional"))
    )
    (net (code "49") (name "/RC_CH1_ST") (class "Default")
      (node (ref "R20") (pin "2") (pinfunction "2_2") (pintype "bidirectional"))
      (node (ref "ST") (pin "1") (pinfunction "1_1") (pintype "bidirectional"))
    )
    (net (code "50") (name "/RC_CH2_TH") (class "Default")
      (node (ref "R21") (pin "2") (pinfunction "2_2") (pintype "bidirectional"))
      (node (ref "TH") (pin "1") (pinfunction "1_1") (pintype "bidirectional"))
    )
    (net (code "51") (name "/RECV_CH1") (class "Default")
      (node (ref "R12") (pin "2") (pinfunction "2_2") (pintype "bidirectional"))
      (node (ref "R34") (pin "1") (pinfunction "1_1") (pintype "bidirectional"))
      (node (ref "U$1") (pin "3") (pinfunction "3:B0_3") (pintype "bidirectional"))
    )
    (net (code "52") (name "/RECV_CH2") (class "Default")
      (node (ref "R11") (pin "2") (pinfunction "2_2") (pintype "bidirectional"))
      (node (ref "R35") (pin "1") (pinfunction "1_1") (pintype "bidirectional"))
      (node (ref "U$1") (pin "6") (pinfunction "6:B1_6") (pintype "bidirectional"))
    )
    (net (code "53") (name "/RESET_SIG") (class "Default")
      (node (ref "R31") (pin "2") (pinfunction "2_2") (pintype "bidirectional"))
      (node (ref "U7") (pin "17") (pinfunction "RES#_17") (pintype "bidirectional"))
    )
    (net (code "54") (name "/RX_JETSON") (class "Default")
      (node (ref "GPIO40") (pin "10") (pinfunction "RX_10") (pintype "bidirectional"))
      (node (ref "R63") (pin "2") (pinfunction "2_2") (pintype "bidirectional"))
    )
    (net (code "55") (name "/SCL") (class "Default")
      (node (ref "GPIO40") (pin "5") (pinfunction "SCL_5") (pintype "bidirectional"))
      (node (ref "I2C") (pin "SCL") (pinfunction "SCL_SCL") (pintype "bidirectional"))
      (node (ref "IC2") (pin "26") (pinfunction "SCL_26") (pintype "bidirectional"))
      (node (ref "R22") (pin "1") (pinfunction "1_1") (pintype "bidirectional"))
      (node (ref "U$14") (pin "15:GPIO9") (pinfunction "15:GPIO9_15:GPIO9") (pintype "bidirectional"))
      (node (ref "U$14") (pin "15:GPIO9_L") (pinfunction "15:GPIO9_15:GPIO9_L") (pintype "bidirectional"))
      (node (ref "U6") (pin "19") (pinfunction "19:H_SCL/SCK/RX_19") (pintype "bidirectional"))
      (node (ref "U7") (pin "13") (pinfunction "D0_13") (pintype "bidirectional"))
    )
    (net (code "56") (name "/SCLK") (class "Default")
      (node (ref "GPIO40") (pin "23") (pinfunction "SCLK_23") (pintype "bidirectional"))
    )
    (net (code "57") (name "/SDA") (class "Default")
      (node (ref "GPIO40") (pin "3") (pinfunction "SDA_3") (pintype "bidirectional"))
      (node (ref "I2C") (pin "SDA") (pinfunction "SDA_SDA") (pintype "bidirectional"))
      (node (ref "IC2") (pin "27") (pinfunction "SDA_27") (pintype "bidirectional"))
      (node (ref "R23") (pin "1") (pinfunction "1_1") (pintype "bidirectional"))
      (node (ref "U$14") (pin "12:GPIO8") (pinfunction "12:GPIO8_12:GPIO8") (pintype "bidirectional"))
      (node (ref "U$14") (pin "12:GPIO8_L") (pinfunction "12:GPIO8_12:GPIO8_L") (pintype "bidirectional"))
      (node (ref "U6") (pin "20") (pinfunction "20:H_SDA/H_MISO/TX_20") (pintype "bidirectional"))
      (node (ref "U7") (pin "11") (pinfunction "D2_11") (pintype "bidirectional"))
      (node (ref "U7") (pin "12") (pinfunction "D1_12") (pintype "bidirectional"))
    )
    (net (code "58") (name "/SEL") (class "Default")
      (node (ref "C26") (pin "2") (pinfunction "2_2") (pintype "passive"))
      (node (ref "R5") (pin "1") (pinfunction "1_1") (pintype "bidirectional"))
      (node (ref "T1") (pin "3") (pinfunction "3:OUT(COLLECTOR)_3") (pintype "output"))
      (node (ref "U$1") (pin "1") (pinfunction "1:S_1") (pintype "bidirectional"))
    )
    (net (code "59") (name "/SENSE1_ESC") (class "Default")
      (node (ref "ESC_CON") (pin "2") (pinfunction "2:SENSOR1_2") (pintype "bidirectional"))
      (node (ref "R50") (pin "2") (pinfunction "2_2") (pintype "bidirectional"))
      (node (ref "U$3") (pin "1") (pinfunction "1:1A_1") (pintype "input"))
    )
    (net (code "60") (name "/SENSE1_MOTOR") (class "Default")
      (node (ref "MOTOR") (pin "2") (pinfunction "2:SENSOR1_2") (pintype "bidirectional"))
      (node (ref "R50") (pin "1") (pinfunction "1_1") (pintype "bidirectional"))
    )
    (net (code "61") (name "/SENSE2_ESC") (class "Default")
      (node (ref "ESC_CON") (pin "3") (pinfunction "3:SENSOR2_3") (pintype "bidirectional"))
      (node (ref "R51") (pin "2") (pinfunction "2_2") (pintype "bidirectional"))
      (node (ref "U$3") (pin "6") (pinfunction "6:3A_6") (pintype "input"))
    )
    (net (code "62") (name "/SENSE2_MOTOR") (class "Default")
      (node (ref "MOTOR") (pin "3") (pinfunction "3:SENSOR2_3") (pintype "bidirectional"))
      (node (ref "R51") (pin "1") (pinfunction "1_1") (pintype "bidirectional"))
    )
    (net (code "63") (name "/SENSE3_ESC") (class "Default")
      (node (ref "ESC_CON") (pin "4") (pinfunction "4:SENSOR3_4") (pintype "bidirectional"))
      (node (ref "R52") (pin "2") (pinfunction "2_2") (pintype "bidirectional"))
      (node (ref "U$3") (pin "3") (pinfunction "3:2A_3") (pintype "input"))
    )
    (net (code "64") (name "/SENSE3_MOTOR") (class "Default")
      (node (ref "MOTOR") (pin "4") (pinfunction "4:SENSOR3_4") (pintype "bidirectional"))
      (node (ref "R52") (pin "1") (pinfunction "1_1") (pintype "bidirectional"))
    )
    (net (code "65") (name "/SIGNAL_SELCET") (class "Default")
      (node (ref "T1") (pin "2") (pinfunction "2:IN(BASE)_2") (pintype "input"))
      (node (ref "U$14") (pin "17:GPIO47") (pinfunction "17:GPIO47_17:GPIO47") (pintype "bidirectional"))
      (node (ref "U$14") (pin "17:GPIO47_R") (pinfunction "17:GPIO47_17:GPIO47_R") (pintype "bidirectional"))
    )
    (net (code "66") (name "/TX_JETSON") (class "Default")
      (node (ref "GPIO40") (pin "8") (pinfunction "TX_8") (pintype "bidirectional"))
      (node (ref "R64") (pin "2") (pinfunction "2_2") (pintype "bidirectional"))
    )
    (net (code "67") (name "3V3_JETSON") (class "Default")
      (node (ref "C11") (pin "2") (pinfunction "2_2") (pintype "passive"))
      (node (ref "C15") (pin "2") (pinfunction "2_2") (pintype "passive"))
      (node (ref "C17") (pin "2") (pinfunction "2_2") (pintype "passive"))
      (node (ref "C18") (pin "2") (pinfunction "2_2") (pintype "passive"))
      (node (ref "C2") (pin "2") (pinfunction "2_2") (pintype "passive"))
      (node (ref "C20") (pin "2") (pinfunction "2_2") (pintype "passive"))
      (node (ref "C27") (pin "2") (pinfunction "2_2") (pintype "passive"))
      (node (ref "C28") (pin "2") (pinfunction "2_2") (pintype "passive"))
      (node (ref "C29") (pin "2") (pinfunction "2_2") (pintype "passive"))
      (node (ref "C30") (pin "2") (pinfunction "2_2") (pintype "passive"))
      (node (ref "C4") (pin "2") (pinfunction "2_2") (pintype "passive"))
      (node (ref "C9") (pin "2") (pinfunction "2_2") (pintype "passive"))
      (node (ref "D1") (pin "CATHODE") (pinfunction "CATHODE_CATHODE") (pintype "bidirectional"))
      (node (ref "GP13") (pin "3V3") (pinfunction "3:3V3_3V3") (pintype "bidirectional"))
      (node (ref "GPIO40") (pin "1") (pinfunction "3V3_1") (pintype "bidirectional"))
      (node (ref "GPIO40") (pin "17") (pinfunction "3V3_17") (pintype "bidirectional"))
      (node (ref "IC2") (pin "28") (pinfunction "VDD_28") (pintype "bidirectional"))
      (node (ref "R19") (pin "1") (pinfunction "1_1") (pintype "bidirectional"))
      (node (ref "R22") (pin "2") (pinfunction "2_2") (pintype "bidirectional"))
      (node (ref "R23") (pin "2") (pinfunction "2_2") (pintype "bidirectional"))
      (node (ref "R25") (pin "1") (pinfunction "1_1") (pintype "bidirectional"))
      (node (ref "R37") (pin "2") (pinfunction "2_2") (pintype "bidirectional"))
      (node (ref "R39") (pin "1") (pinfunction "1_1") (pintype "bidirectional"))
      (node (ref "R43") (pin "1") (pinfunction "1_1") (pintype "bidirectional"))
      (node (ref "R44") (pin "1") (pinfunction "1_1") (pintype "bidirectional"))
      (node (ref "R47") (pin "2") (pinfunction "2_2") (pintype "bidirectional"))
      (node (ref "R48") (pin "2") (pinfunction "2_2") (pintype "bidirectional"))
      (node (ref "R59") (pin "2") (pinfunction "2_2") (pintype "bidirectional"))
      (node (ref "R69") (pin "2") (pinfunction "2_2") (pintype "bidirectional"))
      (node (ref "R70") (pin "2") (pinfunction "2_2") (pintype "bidirectional"))
      (node (ref "R72") (pin "2") (pinfunction "2_2") (pintype "bidirectional"))
      (node (ref "R73") (pin "1") (pinfunction "1_1") (pintype "bidirectional"))
      (node (ref "R80") (pin "2") (pinfunction "2_2") (pintype "bidirectional"))
      (node (ref "U$11") (pin "#1") (pinfunction "1:INH_#1") (pintype "bidirectional"))
      (node (ref "U$11") (pin "#4") (pinfunction "4:VCC_#4") (pintype "bidirectional"))
      (node (ref "U$5") (pin "8") (pinfunction "8:VCC_8") (pintype "power_in"))
      (node (ref "U1") (pin "8") (pinfunction "8:VDD__8") (pintype "bidirectional"))
      (node (ref "U2") (pin "4") (pinfunction "COL_4") (pintype "passive"))
      (node (ref "U3") (pin "4") (pinfunction "COL_4") (pintype "passive"))
      (node (ref "U4") (pin "4") (pinfunction "COL_4") (pintype "passive"))
      (node (ref "U6") (pin "28") (pinfunction "28:VDDIO_28") (pintype "power_in"))
      (node (ref "U6") (pin "3") (pinfunction "3:VDD_3") (pintype "power_in"))
      (node (ref "U7") (pin "22") (pinfunction "VDD_22") (pintype "bidirectional"))
      (node (ref "U7") (pin "25") (pinfunction "VBAT_25") (pintype "bidirectional"))
    )
    (net (code "68") (name "5V") (class "Default")
      (node (ref "C1") (pin "2") (pinfunction "2_2") (pintype "passive"))
      (node (ref "C10") (pin "2") (pinfunction "2_2") (pintype "passive"))
      (node (ref "C14") (pin "2") (pinfunction "2_2") (pintype "passive"))
      (node (ref "D3") (pin "A") (pinfunction "ANODE_A") (pintype "passive"))
      (node (ref "EXT1") (pin "2:5V") (pinfunction "2:5V_2:5V") (pintype "power_in"))
      (node (ref "EXT2") (pin "2") (pinfunction "2:5V_2") (pintype "bidirectional"))
      (node (ref "GP12") (pin "VCC") (pinfunction "VCC_VCC") (pintype "bidirectional"))
      (node (ref "GP13") (pin "5V") (pinfunction "2:5V_5V") (pintype "bidirectional"))
      (node (ref "GPIO40") (pin "2") (pinfunction "5V_2") (pintype "bidirectional"))
      (node (ref "I2C") (pin "5V") (pinfunction "VCC_5V") (pintype "bidirectional"))
      (node (ref "LED1") (pin "VCC") (pinfunction "VCC_VCC") (pintype "bidirectional"))
      (node (ref "R28") (pin "2") (pinfunction "2_2") (pintype "bidirectional"))
      (node (ref "SPI-LED") (pin "5V") (pinfunction "VCC_5V") (pintype "bidirectional"))
      (node (ref "U$10") (pin "5") (pinfunction "5:VCC_5") (pintype "power_in"))
      (node (ref "U$9") (pin "5") (pinfunction "5:VCC_5") (pintype "power_in"))
    )
    (net (code "69") (name "5VL_JETSON") (class "Default")
      (node (ref "D3") (pin "K") (pinfunction "CATHODE_K") (pintype "passive"))
      (node (ref "U$14") (pin "21:5V0") (pinfunction "21:5V0_21:5V0") (pintype "power_in"))
      (node (ref "U$14") (pin "21:5V0_L") (pinfunction "21:5V0_21:5V0_L") (pintype "power_in"))
    )
    (net (code "70") (name "GND") (class "Default")
      (node (ref "1") (pin "3") (pinfunction "3_3") (pintype "power_in"))
      (node (ref "C1") (pin "1") (pinfunction "1_1") (pintype "passive"))
      (node (ref "C10") (pin "1") (pinfunction "1_1") (pintype "passive"))
      (node (ref "C11") (pin "1") (pinfunction "1_1") (pintype "passive"))
      (node (ref "C12") (pin "1") (pinfunction "1_1") (pintype "passive"))
      (node (ref "C13") (pin "1") (pinfunction "1_1") (pintype "passive"))
      (node (ref "C14") (pin "1") (pinfunction "1_1") (pintype "passive"))
      (node (ref "C15") (pin "1") (pinfunction "1_1") (pintype "passive"))
      (node (ref "C16") (pin "1") (pinfunction "1_1") (pintype "passive"))
      (node (ref "C17") (pin "1") (pinfunction "1_1") (pintype "passive"))
      (node (ref "C18") (pin "1") (pinfunction "1_1") (pintype "passive"))
      (node (ref "C2") (pin "1") (pinfunction "1_1") (pintype "passive"))
      (node (ref "C20") (pin "1") (pinfunction "1_1") (pintype "passive"))
      (node (ref "C21") (pin "1") (pinfunction "1_1") (pintype "passive"))
      (node (ref "C23") (pin "1") (pinfunction "1_1") (pintype "passive"))
      (node (ref "C24") (pin "2") (pinfunction "2_2") (pintype "passive"))
      (node (ref "C25") (pin "2") (pinfunction "2_2") (pintype "passive"))
      (node (ref "C26") (pin "1") (pinfunction "1_1") (pintype "passive"))
      (node (ref "C27") (pin "1") (pinfunction "1_1") (pintype "passive"))
      (node (ref "C28") (pin "1") (pinfunction "1_1") (pintype "passive"))
      (node (ref "C29") (pin "1") (pinfunction "1_1") (pintype "passive"))
      (node (ref "C3") (pin "1") (pinfunction "1_1") (pintype "passive"))
      (node (ref "C30") (pin "1") (pinfunction "1_1") (pintype "passive"))
      (node (ref "C4") (pin "1") (pinfunction "1_1") (pintype "passive"))
      (node (ref "C5") (pin "1") (pinfunction "1_1") (pintype "passive"))
      (node (ref "C6") (pin "1") (pinfunction "1_1") (pintype "passive"))
      (node (ref "C7") (pin "1") (pinfunction "1_1") (pintype "passive"))
      (node (ref "C8") (pin "1") (pinfunction "1_1") (pintype "passive"))
      (node (ref "C9") (pin "1") (pinfunction "1_1") (pintype "passive"))
      (node (ref "CH2") (pin "3") (pinfunction "3_3") (pintype "power_in"))
      (node (ref "CH3") (pin "3") (pinfunction "3_3") (pintype "power_in"))
      (node (ref "CH4") (pin "3") (pinfunction "3_3") (pintype "power_in"))
      (node (ref "CH5") (pin "3") (pinfunction "3_3") (pintype "power_in"))
      (node (ref "ESC_CON") (pin "1") (pinfunction "1:GND_1") (pintype "bidirectional"))
      (node (ref "EXT1") (pin "1:GND") (pinfunction "1:GND_1:GND") (pintype "power_in"))
      (node (ref "EXT1") (pin "8:GND") (pinfunction "8:GND_8:GND") (pintype "power_in"))
      (node (ref "EXT2") (pin "1") (pinfunction "1:GND_1") (pintype "bidirectional"))
      (node (ref "GP12") (pin "GND") (pinfunction "GND_GND") (pintype "bidirectional"))
      (node (ref "GP13") (pin "GND") (pinfunction "1:GND_GND") (pintype "bidirectional"))
      (node (ref "GPIO40") (pin "14") (pinfunction "GND_14") (pintype "bidirectional"))
      (node (ref "GPIO40") (pin "20") (pinfunction "GND_20") (pintype "bidirectional"))
      (node (ref "GPIO40") (pin "25") (pinfunction "GND_25") (pintype "bidirectional"))
      (node (ref "GPIO40") (pin "30") (pinfunction "GND_30") (pintype "bidirectional"))
      (node (ref "GPIO40") (pin "34") (pinfunction "GND_34") (pintype "bidirectional"))
      (node (ref "GPIO40") (pin "39") (pinfunction "GND_39") (pintype "bidirectional"))
      (node (ref "GPIO40") (pin "9") (pinfunction "GND_9") (pintype "bidirectional"))
      (node (ref "I2C") (pin "GND") (pinfunction "GND_GND") (pintype "bidirectional"))
      (node (ref "IC1") (pin "2") (pinfunction "GND_2") (pintype "power_in"))
      (node (ref "IC2") (pin "1") (pinfunction "A0_1") (pintype "bidirectional"))
      (node (ref "IC2") (pin "14") (pinfunction "VSS_14") (pintype "bidirectional"))
      (node (ref "IC2") (pin "2") (pinfunction "A1_2") (pintype "bidirectional"))
      (node (ref "IC2") (pin "24") (pinfunction "A5_24") (pintype "bidirectional"))
      (node (ref "IC2") (pin "3") (pinfunction "A2_3") (pintype "bidirectional"))
      (node (ref "IC2") (pin "4") (pinfunction "A3_4") (pintype "bidirectional"))
      (node (ref "IC2") (pin "5") (pinfunction "A4_5") (pintype "bidirectional"))
      (node (ref "LED1") (pin "GND") (pinfunction "GND_GND") (pintype "bidirectional"))
      (node (ref "MOTOR") (pin "1") (pinfunction "1:GND_1") (pintype "bidirectional"))
      (node (ref "Q1") (pin "S") (pinfunction "S_S") (pintype "passive"))
      (node (ref "Q2") (pin "S") (pinfunction "S_S") (pintype "passive"))
      (node (ref "Q3") (pin "S") (pinfunction "S_S") (pintype "passive"))
      (node (ref "Q4") (pin "S") (pinfunction "S_S") (pintype "passive"))
      (node (ref "Q5") (pin "S") (pinfunction "S_S") (pintype "passive"))
      (node (ref "R1") (pin "1") (pinfunction "1_1") (pintype "bidirectional"))
      (node (ref "R13") (pin "2") (pinfunction "2_2") (pintype "bidirectional"))
      (node (ref "R17") (pin "1") (pinfunction "1_1") (pintype "bidirectional"))
      (node (ref "R24") (pin "2") (pinfunction "2_2") (pintype "bidirectional"))
      (node (ref "R28") (pin "1") (pinfunction "1_1") (pintype "bidirectional"))
      (node (ref "R3") (pin "1") (pinfunction "1_1") (pintype "bidirectional"))
      (node (ref "R32") (pin "2") (pinfunction "2_2") (pintype "bidirectional"))
      (node (ref "R33") (pin "2") (pinfunction "2_2") (pintype "bidirectional"))
      (node (ref "R36") (pin "1") (pinfunction "1_1") (pintype "bidirectional"))
      (node (ref "R40") (pin "2") (pinfunction "2_2") (pintype "bidirectional"))
      (node (ref "R41") (pin "2") (pinfunction "2_2") (pintype "bidirectional"))
      (node (ref "R42") (pin "2") (pinfunction "2_2") (pintype "bidirectional"))
      (node (ref "R45") (pin "1") (pinfunction "1_1") (pintype "bidirectional"))
      (node (ref "R46") (pin "2") (pinfunction "2_2") (pintype "bidirectional"))
      (node (ref "R55") (pin "2") (pinfunction "2_2") (pintype "bidirectional"))
      (node (ref "R58") (pin "1") (pinfunction "1_1") (pintype "bidirectional"))
      (node (ref "R6") (pin "2") (pinfunction "2_2") (pintype "bidirectional"))
      (node (ref "R60") (pin "2") (pinfunction "2_2") (pintype "bidirectional"))
      (node (ref "R62") (pin "2") (pinfunction "2_2") (pintype "bidirectional"))
      (node (ref "R65") (pin "1") (pinfunction "1_1") (pintype "bidirectional"))
      (node (ref "R66") (pin "2") (pinfunction "2_2") (pintype "bidirectional"))
      (node (ref "R68") (pin "2") (pinfunction "2_2") (pintype "bidirectional"))
      (node (ref "R7") (pin "2") (pinfunction "2_2") (pintype "bidirectional"))
      (node (ref "R9") (pin "1") (pinfunction "1_1") (pintype "bidirectional"))
      (node (ref "SPI-LED") (pin "GND") (pinfunction "GND_GND") (pintype "bidirectional"))
      (node (ref "ST") (pin "3") (pinfunction "3_3") (pintype "power_in"))
      (node (ref "T1") (pin "1") (pinfunction "1:GND(EMITTER)_1") (pintype "passive"))
      (node (ref "TH") (pin "3") (pinfunction "3_3") (pintype "power_in"))
      (node (ref "U$1") (pin "15") (pinfunction "15:E_15") (pintype "bidirectional"))
      (node (ref "U$1") (pin "8") (pinfunction "8:GND_8") (pintype "bidirectional"))
      (node (ref "U$10") (pin "1") (pinfunction "1:OE_1") (pintype "input"))
      (node (ref "U$10") (pin "3") (pinfunction "3:GND_3") (pintype "power_in"))
      (node (ref "U$11") (pin "#2") (pinfunction "2:CASE_GND_#2") (pintype "bidirectional"))
      (node (ref "U$14") (pin "1:GND_J3") (pinfunction "1:GND_J3_1:GND_J3") (pintype "bidirectional"))
      (node (ref "U$14") (pin "1:GND_J3R") (pinfunction "1:GND_J3_1:GND_J3R") (pintype "bidirectional"))
      (node (ref "U$14") (pin "21:GND_J3") (pinfunction "21:GND_J3_21:GND_J3") (pintype "power_in"))
      (node (ref "U$14") (pin "21:GND_J3_R") (pinfunction "21:GND_J3_21:GND_J3_R") (pintype "power_in"))
      (node (ref "U$14") (pin "22:GND_J1") (pinfunction "22:GND_J1_22:GND_J1") (pintype "power_in"))
      (node (ref "U$14") (pin "22:GND_J1L") (pinfunction "22:GND_J1_22:GND_J1L") (pintype "power_in"))
      (node (ref "U$14") (pin "22:GND_J3") (pinfunction "22:GND_J3_22:GND_J3") (pintype "power_in"))
      (node (ref "U$14") (pin "22:GND_J3_R") (pinfunction "22:GND_J3_22:GND_J3_R") (pintype "power_in"))
      (node (ref "U$3") (pin "4") (pinfunction "4:GND_4") (pintype "power_in"))
      (node (ref "U$5") (pin "4") (pinfunction "4:GND_4") (pintype "power_in"))
      (node (ref "U$9") (pin "1") (pinfunction "1:OE_1") (pintype "input"))
      (node (ref "U$9") (pin "3") (pinfunction "3:GND_3") (pintype "power_in"))
      (node (ref "U1") (pin "5") (pinfunction "5:GND_5") (pintype "bidirectional"))
      (node (ref "U6") (pin "18") (pinfunction "18:H_CSN_18") (pintype "input"))
      (node (ref "U6") (pin "2") (pinfunction "2:GND_2") (pintype "power_in"))
      (node (ref "U6") (pin "25") (pinfunction "25:GND_25") (pintype "power_in"))
      (node (ref "U6") (pin "5") (pinfunction "5:PS1_5") (pintype "input"))
      (node (ref "U6") (pin "6") (pinfunction "6:PS0/WAKE_6") (pintype "input"))
      (node (ref "U7") (pin "10") (pinfunction "D3_10") (pintype "bidirectional"))
      (node (ref "U7") (pin "14") (pinfunction "E/RD#_14") (pintype "bidirectional"))
      (node (ref "U7") (pin "15") (pinfunction "R/W#_15") (pintype "bidirectional"))
      (node (ref "U7") (pin "18") (pinfunction "CS#_18") (pintype "bidirectional"))
      (node (ref "U7") (pin "19") (pinfunction "BS2_19") (pintype "bidirectional"))
      (node (ref "U7") (pin "2") (pinfunction "VLSS_2") (pintype "bidirectional"))
      (node (ref "U7") (pin "21") (pinfunction "BS0_21") (pintype "bidirectional"))
      (node (ref "U7") (pin "23") (pinfunction "VSS_23") (pintype "bidirectional"))
      (node (ref "U7") (pin "6") (pinfunction "D7_6") (pintype "bidirectional"))
      (node (ref "U7") (pin "7") (pinfunction "D6_7") (pintype "bidirectional"))
      (node (ref "U7") (pin "8") (pinfunction "D5_8") (pintype "bidirectional"))
      (node (ref "U7") (pin "9") (pinfunction "D4_9") (pintype "bidirectional"))
    )
    (net (code "71") (name "M_SENSOR1") (class "Default")
      (node (ref "R47") (pin "1") (pinfunction "1_1") (pintype "bidirectional"))
      (node (ref "U$14") (pin "9:GPIO16") (pinfunction "9:GPIO16_9:GPIO16") (pintype "bidirectional"))
      (node (ref "U$14") (pin "9:GPIO16_L") (pinfunction "9:GPIO16_9:GPIO16_L") (pintype "bidirectional"))
      (node (ref "U$3") (pin "7") (pinfunction "7:1Y_7") (pintype "open_collector"))
    )
    (net (code "72") (name "M_SENSOR2") (class "Default")
      (node (ref "R48") (pin "1") (pinfunction "1_1") (pintype "bidirectional"))
      (node (ref "U$14") (pin "10:GPIO17") (pinfunction "10:GPIO17_10:GPIO17") (pintype "bidirectional"))
      (node (ref "U$14") (pin "10:GPIO17_L") (pinfunction "10:GPIO17_10:GPIO17_L") (pintype "bidirectional"))
      (node (ref "U$3") (pin "2") (pinfunction "2:3Y_2") (pintype "open_collector"))
    )
    (net (code "73") (name "M_SENSOR3") (class "Default")
      (node (ref "R59") (pin "1") (pinfunction "1_1") (pintype "bidirectional"))
      (node (ref "U$14") (pin "11:GPIO18") (pinfunction "11:GPIO18_11:GPIO18") (pintype "bidirectional"))
      (node (ref "U$14") (pin "11:GPIO18_L") (pinfunction "11:GPIO18_11:GPIO18_L") (pintype "bidirectional"))
      (node (ref "U$3") (pin "5") (pinfunction "5:2Y_5") (pintype "open_collector"))
    )
    (net (code "74") (name "Net-(C12-Pad2)") (class "Default")
      (node (ref "C12") (pin "2") (pinfunction "2_2") (pintype "passive"))
      (node (ref "D1") (pin "ANODE") (pinfunction "ANODE_ANODE") (pintype "bidirectional"))
      (node (ref "R25") (pin "2") (pinfunction "2_2") (pintype "bidirectional"))
      (node (ref "R31") (pin "1") (pinfunction "1_1") (pintype "bidirectional"))
    )
    (net (code "75") (name "Net-(CH4-Pad1)") (class "Default")
      (node (ref "CH4") (pin "1") (pinfunction "1_1") (pintype "bidirectional"))
      (node (ref "R54") (pin "2") (pinfunction "2_2") (pintype "bidirectional"))
    )
    (net (code "76") (name "Net-(CH5-Pad1)") (class "Default")
      (node (ref "CH5") (pin "1") (pinfunction "1_1") (pintype "bidirectional"))
      (node (ref "R61") (pin "2") (pinfunction "2_2") (pintype "bidirectional"))
    )
    (net (code "77") (name "Net-(EXT1-Pad3:DOUT)") (class "Default")
      (node (ref "EXT1") (pin "3:DOUT") (pinfunction "3:DOUT_3:DOUT") (pintype "input"))
      (node (ref "R18") (pin "2") (pinfunction "2_2") (pintype "bidirectional"))
      (node (ref "R41") (pin "1") (pinfunction "1_1") (pintype "bidirectional"))
    )
    (net (code "78") (name "Net-(EXT1-Pad4:BCLK)") (class "Default")
      (node (ref "EXT1") (pin "4:BCLK") (pinfunction "4:BCLK_4:BCLK") (pintype "input"))
      (node (ref "R30") (pin "2") (pinfunction "2_2") (pintype "bidirectional"))
    )
    (net (code "79") (name "Net-(EXT1-Pad5:LRCLK)") (class "Default")
      (node (ref "EXT1") (pin "5:LRCLK") (pinfunction "5:LRCLK_5:LRCLK") (pintype "input"))
      (node (ref "R38") (pin "2") (pinfunction "2_2") (pintype "bidirectional"))
    )
    (net (code "80") (name "Net-(IC1-BYPASS)") (class "Default")
      (node (ref "C6") (pin "2") (pinfunction "2_2") (pintype "passive"))
      (node (ref "IC1") (pin "4") (pinfunction "BYPASS_4") (pintype "bidirectional"))
    )
    (net (code "81") (name "Net-(IC2-EXTCLK)") (class "Default")
      (node (ref "C3") (pin "2") (pinfunction "2_2") (pintype "passive"))
      (node (ref "IC2") (pin "25") (pinfunction "EXTCLK_25") (pintype "bidirectional"))
      (node (ref "R1") (pin "2") (pinfunction "2_2") (pintype "bidirectional"))
      (node (ref "U$11") (pin "#3") (pinfunction "3:OUTPUT_#3") (pintype "bidirectional"))
    )
    (net (code "82") (name "Net-(IC2-LED14)") (class "Default")
      (node (ref "IC2") (pin "21") (pinfunction "LED14_21") (pintype "bidirectional"))
      (node (ref "TP2") (pin "TP") (pinfunction "TP_TP") (pintype "passive"))
    )
    (net (code "83") (name "Net-(IC2-OE)") (class "Default")
      (node (ref "IC2") (pin "23") (pinfunction "OE_23") (pintype "bidirectional"))
      (node (ref "R3") (pin "2") (pinfunction "2_2") (pintype "bidirectional"))
    )
    (net (code "84") (name "Net-(Q1-PadG)") (class "Default")
      (node (ref "Q1") (pin "G") (pinfunction "G_G") (pintype "passive"))
      (node (ref "R54") (pin "1") (pinfunction "1_1") (pintype "bidirectional"))
      (node (ref "R55") (pin "1") (pinfunction "1_1") (pintype "bidirectional"))
    )
    (net (code "85") (name "Net-(Q2-PadG)") (class "Default")
      (node (ref "Q2") (pin "G") (pinfunction "G_G") (pintype "passive"))
      (node (ref "R61") (pin "1") (pinfunction "1_1") (pintype "bidirectional"))
      (node (ref "R62") (pin "1") (pinfunction "1_1") (pintype "bidirectional"))
    )
    (net (code "86") (name "Net-(Q3-PadG)") (class "Default")
      (node (ref "Q3") (pin "G") (pinfunction "G_G") (pintype "passive"))
      (node (ref "R24") (pin "1") (pinfunction "1_1") (pintype "bidirectional"))
      (node (ref "R8") (pin "1") (pinfunction "1_1") (pintype "bidirectional"))
    )
    (net (code "87") (name "Net-(Q4-PadG)") (class "Default")
      (node (ref "Q4") (pin "G") (pinfunction "G_G") (pintype "passive"))
      (node (ref "R33") (pin "1") (pinfunction "1_1") (pintype "bidirectional"))
      (node (ref "R35") (pin "2") (pinfunction "2_2") (pintype "bidirectional"))
    )
    (net (code "88") (name "Net-(Q5-PadG)") (class "Default")
      (node (ref "Q5") (pin "G") (pinfunction "G_G") (pintype "passive"))
      (node (ref "R32") (pin "1") (pinfunction "1_1") (pintype "bidirectional"))
      (node (ref "R34") (pin "2") (pinfunction "2_2") (pintype "bidirectional"))
    )
    (net (code "89") (name "Net-(R7-Pad1)") (class "Default")
      (node (ref "R7") (pin "1") (pinfunction "1_1") (pintype "bidirectional"))
      (node (ref "RCPWR") (pin "CATHODE") (pinfunction "CATHODE_CATHODE") (pintype "passive"))
    )
    (net (code "90") (name "Net-(R63-Pad1)") (class "Default")
      (node (ref "R63") (pin "1") (pinfunction "1_1") (pintype "bidirectional"))
      (node (ref "U$14") (pin "2:GPIO43") (pinfunction "2:GPIO43/U0TXD_2:GPIO43") (pintype "bidirectional"))
      (node (ref "U$14") (pin "2:GPIO43_R") (pinfunction "2:GPIO43/U0TXD_2:GPIO43_R") (pintype "bidirectional"))
    )
    (net (code "91") (name "Net-(R64-Pad1)") (class "Default")
      (node (ref "R64") (pin "1") (pinfunction "1_1") (pintype "bidirectional"))
      (node (ref "U$14") (pin "3:GPIO44") (pinfunction "3:GPIO44/U0RXD_3:GPIO44") (pintype "bidirectional"))
      (node (ref "U$14") (pin "3:GPIO44_R") (pinfunction "3:GPIO44/U0RXD_3:GPIO44_R") (pintype "bidirectional"))
    )
    (net (code "92") (name "Net-(R78-Pad2)") (class "Default")
      (node (ref "R78") (pin "2") (pinfunction "2_2") (pintype "bidirectional"))
      (node (ref "U$14") (pin "16:GPIO10") (pinfunction "16:GPIO10_16:GPIO10") (pintype "bidirectional"))
      (node (ref "U$14") (pin "16:GPIO10_L") (pinfunction "16:GPIO10_16:GPIO10_L") (pintype "bidirectional"))
    )
    (net (code "93") (name "Net-(R79-Pad2)") (class "Default")
      (node (ref "R79") (pin "2") (pinfunction "2_2") (pintype "bidirectional"))
      (node (ref "U$14") (pin "19:GPIO13") (pinfunction "19:GPIO13_19:GPIO13") (pintype "bidirectional"))
      (node (ref "U$14") (pin "19:GPIO13_L") (pinfunction "19:GPIO13_19:GPIO13_L") (pintype "bidirectional"))
    )
    (net (code "94") (name "Net-(U$1-2:A0)") (class "Default")
      (node (ref "R75") (pin "2") (pinfunction "2_2") (pintype "bidirectional"))
      (node (ref "U$1") (pin "2") (pinfunction "2:A0_2") (pintype "bidirectional"))
      (node (ref "U$5") (pin "7") (pinfunction "7:1Y_7") (pintype "open_collector"))
    )
    (net (code "95") (name "Net-(U$1-5:A1)") (class "Default")
      (node (ref "R74") (pin "2") (pinfunction "2_2") (pintype "bidirectional"))
      (node (ref "U$1") (pin "5") (pinfunction "5:A1_5") (pintype "bidirectional"))
      (node (ref "U$5") (pin "5") (pinfunction "5:2Y_5") (pintype "open_collector"))
    )
    (net (code "96") (name "Net-(U$1-10:B2)") (class "Default")
      (node (ref "R45") (pin "2") (pinfunction "2_2") (pintype "bidirectional"))
      (node (ref "U$1") (pin "10") (pinfunction "10:B2_10") (pintype "bidirectional"))
    )
    (net (code "97") (name "Net-(U$1-11:A2)") (class "Default")
      (node (ref "R17") (pin "2") (pinfunction "2_2") (pintype "bidirectional"))
      (node (ref "U$1") (pin "11") (pinfunction "11:A2_11") (pintype "bidirectional"))
    )
    (net (code "98") (name "Net-(U$1-13:B3)") (class "Default")
      (node (ref "R9") (pin "2") (pinfunction "2_2") (pintype "bidirectional"))
      (node (ref "U$1") (pin "13") (pinfunction "13:B3_13") (pintype "bidirectional"))
    )
    (net (code "99") (name "Net-(U$1-14:A3)") (class "Default")
      (node (ref "R65") (pin "2") (pinfunction "2_2") (pintype "bidirectional"))
      (node (ref "U$1") (pin "14") (pinfunction "14:A3_14") (pintype "bidirectional"))
    )
    (net (code "100") (name "Net-(U$5-6:3A)") (class "Default")
      (node (ref "R73") (pin "2") (pinfunction "2_2") (pintype "bidirectional"))
      (node (ref "U$5") (pin "6") (pinfunction "6:3A_6") (pintype "input"))
    )
    (net (code "101") (name "Net-(U$9-4:Y)") (class "Default")
      (node (ref "LED1") (pin "SDI") (pinfunction "SDI_SDI") (pintype "bidirectional"))
      (node (ref "U$9") (pin "4") (pinfunction "4:Y_4") (pintype "output"))
    )
    (net (code "102") (name "Net-(U$10-4:Y)") (class "Default")
      (node (ref "LED1") (pin "CKI") (pinfunction "CKI_CKI") (pintype "bidirectional"))
      (node (ref "U$10") (pin "4") (pinfunction "4:Y_4") (pintype "output"))
    )
    (net (code "103") (name "Net-(U$14-1:3V3-Pad1:3V3_L)") (class "Default")
      (node (ref "U$14") (pin "1:3V3") (pinfunction "1:3V3_1:3V3") (pintype "power_in"))
      (node (ref "U$14") (pin "1:3V3_L") (pinfunction "1:3V3_1:3V3_L") (pintype "power_in"))
    )
    (net (code "104") (name "Net-(U$14-2:3V3-Pad2:3V3_L)") (class "Default")
      (node (ref "U$14") (pin "2:3V3") (pinfunction "2:3V3_2:3V3") (pintype "power_in"))
      (node (ref "U$14") (pin "2:3V3_L") (pinfunction "2:3V3_2:3V3_L") (pintype "power_in"))
    )
    (net (code "105") (name "Net-(U$14-3:RST(CHIP_PU)-Pad3:RST)") (class "Default")
      (node (ref "U$14") (pin "3:RST") (pinfunction "3:RST(CHIP_PU)_3:RST") (pintype "input"))
      (node (ref "U$14") (pin "3:RST_L") (pinfunction "3:RST(CHIP_PU)_3:RST_L") (pintype "input"))
    )
    (net (code "106") (name "Net-(U$14-4:GPIO1-Pad4:GPIO1_R)") (class "Default")
      (node (ref "U$14") (pin "4:GPIO1") (pinfunction "4:GPIO1_4:GPIO1") (pintype "bidirectional"))
      (node (ref "U$14") (pin "4:GPIO1_R") (pinfunction "4:GPIO1_4:GPIO1_R") (pintype "bidirectional"))
    )
    (net (code "107") (name "Net-(U$14-5:GPOP2-Pad5:GPIO2)") (class "Default")
      (node (ref "U$14") (pin "5:GPIO2") (pinfunction "5:GPOP2_5:GPIO2") (pintype "bidirectional"))
      (node (ref "U$14") (pin "5:GPIO2_R") (pinfunction "5:GPOP2_5:GPIO2_R") (pintype "bidirectional"))
    )
    (net (code "108") (name "Net-(U$14-6:GPIO42-Pad6:GPIO42_R)") (class "Default")
      (node (ref "U$14") (pin "6:GPIO42") (pinfunction "6:GPIO42_6:GPIO42") (pintype "bidirectional"))
      (node (ref "U$14") (pin "6:GPIO42_R") (pinfunction "6:GPIO42_6:GPIO42_R") (pintype "bidirectional"))
    )
    (net (code "109") (name "Net-(U$14-7:GPIO41-Pad7:GPIO41_R)") (class "Default")
      (node (ref "U$14") (pin "7:GPIO41") (pinfunction "7:GPIO41_7:GPIO41") (pintype "bidirectional"))
      (node (ref "U$14") (pin "7:GPIO41_R") (pinfunction "7:GPIO41_7:GPIO41_R") (pintype "bidirectional"))
    )
    (net (code "110") (name "Net-(U$14-8:GPIO40-Pad8:GPIO40_R)") (class "Default")
      (node (ref "U$14") (pin "8:GPIO40") (pinfunction "8:GPIO40_8:GPIO40") (pintype "bidirectional"))
      (node (ref "U$14") (pin "8:GPIO40_R") (pinfunction "8:GPIO40_8:GPIO40_R") (pintype "bidirectional"))
    )
    (net (code "111") (name "Net-(U$14-9:GPIO39-Pad9:GPIO39_R)") (class "Default")
      (node (ref "U$14") (pin "9:GPIO39") (pinfunction "9:GPIO39_9:GPIO39") (pintype "bidirectional"))
      (node (ref "U$14") (pin "9:GPIO39_R") (pinfunction "9:GPIO39_9:GPIO39_R") (pintype "bidirectional"))
    )
    (net (code "112") (name "Net-(U$14-10:GPIO38-Pad10:GPIO38_R)") (class "Default")
      (node (ref "U$14") (pin "10:GPIO38") (pinfunction "10:GPIO38_10:GPIO38") (pintype "bidirectional"))
      (node (ref "U$14") (pin "10:GPIO38_R") (pinfunction "10:GPIO38_10:GPIO38_R") (pintype "bidirectional"))
    )
    (net (code "113") (name "Net-(U$14-11:GPIO37-Pad11:GPIO37_R)") (class "Default")
      (node (ref "U$14") (pin "11:GPIO37") (pinfunction "11:GPIO37_11:GPIO37") (pintype "bidirectional"))
      (node (ref "U$14") (pin "11:GPIO37_R") (pinfunction "11:GPIO37_11:GPIO37_R") (pintype "bidirectional"))
    )
    (net (code "114") (name "Net-(U$14-12:GPIO36-Pad12:GPIO36_R)") (class "Default")
      (node (ref "U$14") (pin "12:GPIO36") (pinfunction "12:GPIO36_12:GPIO36") (pintype "bidirectional"))
      (node (ref "U$14") (pin "12:GPIO36_R") (pinfunction "12:GPIO36_12:GPIO36_R") (pintype "bidirectional"))
    )
    (net (code "115") (name "Net-(U$14-13:GPIO3{slash}JTAG-Pad13:GPIO3)") (class "Default")
      (node (ref "U$14") (pin "13:GPIO3") (pinfunction "13:GPIO3/JTAG_13:GPIO3") (pintype "input"))
      (node (ref "U$14") (pin "13:GPIO3_L") (pinfunction "13:GPIO3/JTAG_13:GPIO3_L") (pintype "input"))
    )
    (net (code "116") (name "Net-(U$14-13:GPIO35-Pad13:GPIO35_R)") (class "Default")
      (node (ref "U$14") (pin "13:GPIO35") (pinfunction "13:GPIO35_13:GPIO35") (pintype "bidirectional"))
      (node (ref "U$14") (pin "13:GPIO35_R") (pinfunction "13:GPIO35_13:GPIO35_R") (pintype "bidirectional"))
    )
    (net (code "117") (name "Net-(U$14-14:GPIO0{slash}BOOT-Pad14:GPIO0)") (class "Default")
      (node (ref "U$14") (pin "14:GPIO0") (pinfunction "14:GPIO0/BOOT_14:GPIO0") (pintype "input"))
      (node (ref "U$14") (pin "14:GPIO0_R") (pinfunction "14:GPIO0/BOOT_14:GPIO0_R") (pintype "input"))
    )
    (net (code "118") (name "Net-(U$14-14:GPIO46{slash}LOG-Pad14:GPIO46)") (class "Default")
      (node (ref "U$14") (pin "14:GPIO46") (pinfunction "14:GPIO46/LOG_14:GPIO46") (pintype "input"))
      (node (ref "U$14") (pin "14:GPIO46_L") (pinfunction "14:GPIO46/LOG_14:GPIO46_L") (pintype "input"))
    )
    (net (code "119") (name "Net-(U$14-16:GPIO48-Pad16:GPIO48_R)") (class "Default")
      (node (ref "U$14") (pin "16:GPIO48") (pinfunction "16:GPIO48_16:GPIO48") (pintype "bidirectional"))
      (node (ref "U$14") (pin "16:GPIO48_R") (pinfunction "16:GPIO48_16:GPIO48_R") (pintype "bidirectional"))
    )
    (net (code "120") (name "Net-(U$14-18:GPIO21-Pad18:GPIO21_R)") (class "Default")
      (node (ref "U$14") (pin "18:GPIO21") (pinfunction "18:GPIO21_18:GPIO21") (pintype "bidirectional"))
      (node (ref "U$14") (pin "18:GPIO21_R") (pinfunction "18:GPIO21_18:GPIO21_R") (pintype "bidirectional"))
    )
    (net (code "121") (name "Net-(U$14-19:GPIO20{slash}USBD+-Pad19:GPIO20)") (class "Default")
      (node (ref "U$14") (pin "19:GPIO20") (pinfunction "19:GPIO20/USBD+_19:GPIO20") (pintype "bidirectional"))
      (node (ref "U$14") (pin "19:GPIO20_R") (pinfunction "19:GPIO20/USBD+_19:GPIO20_R") (pintype "bidirectional"))
    )
    (net (code "122") (name "Net-(U$14-20:GPIO14-Pad20:GPIO14_L)") (class "Default")
      (node (ref "U$14") (pin "20:GPIO14") (pinfunction "20:GPIO14_20:GPIO14") (pintype "bidirectional"))
      (node (ref "U$14") (pin "20:GPIO14_L") (pinfunction "20:GPIO14_20:GPIO14_L") (pintype "bidirectional"))
    )
    (net (code "123") (name "Net-(U$14-20:GPIO19{slash}USBD--Pad20:GPIO19)") (class "Default")
      (node (ref "U$14") (pin "20:GPIO19") (pinfunction "20:GPIO19/USBD-_20:GPIO19") (pintype "bidirectional"))
      (node (ref "U$14") (pin "20:GPIO19_R") (pinfunction "20:GPIO19/USBD-_20:GPIO19_R") (pintype "bidirectional"))
    )
    (net (code "124") (name "Net-(U1-1:AN1)") (class "Default")
      (node (ref "R16") (pin "1") (pinfunction "1_1") (pintype "bidirectional"))
      (node (ref "R29") (pin "1") (pinfunction "1_1") (pintype "bidirectional"))
      (node (ref "U1") (pin "1") (pinfunction "1:AN1_1") (pintype "bidirectional"))
    )
    (net (code "125") (name "Net-(U1-2:CA1)") (class "Default")
      (node (ref "Q5") (pin "D") (pinfunction "D_D") (pintype "passive"))
      (node (ref "R29") (pin "2") (pinfunction "2_2") (pintype "bidirectional"))
      (node (ref "U1") (pin "2") (pinfunction "2:CA1_2") (pintype "bidirectional"))
    )
    (net (code "126") (name "Net-(U1-3:CA2)") (class "Default")
      (node (ref "Q4") (pin "D") (pinfunction "D_D") (pintype "passive"))
      (node (ref "R27") (pin "1") (pinfunction "1_1") (pintype "bidirectional"))
      (node (ref "U1") (pin "3") (pinfunction "3:CA2_3") (pintype "bidirectional"))
    )
    (net (code "127") (name "Net-(U1-4:AN2)") (class "Default")
      (node (ref "R15") (pin "1") (pinfunction "1_1") (pintype "bidirectional"))
      (node (ref "R27") (pin "2") (pinfunction "2_2") (pintype "bidirectional"))
      (node (ref "U1") (pin "4") (pinfunction "4:AN2_4") (pintype "bidirectional"))
    )
    (net (code "128") (name "Net-(U2-A)") (class "Default")
      (node (ref "R26") (pin "1") (pinfunction "1_1") (pintype "bidirectional"))
      (node (ref "U2") (pin "1") (pinfunction "A_1") (pintype "passive"))
    )
    (net (code "129") (name "Net-(U2-C)") (class "Default")
      (node (ref "Q3") (pin "D") (pinfunction "D_D") (pintype "passive"))
      (node (ref "R53") (pin "2") (pinfunction "2_2") (pintype "bidirectional"))
      (node (ref "U2") (pin "2") (pinfunction "C_2") (pintype "passive"))
    )
    (net (code "130") (name "Net-(U3-A)") (class "Default")
      (node (ref "R56") (pin "1") (pinfunction "1_1") (pintype "bidirectional"))
      (node (ref "U3") (pin "1") (pinfunction "A_1") (pintype "passive"))
    )
    (net (code "131") (name "Net-(U3-C)") (class "Default")
      (node (ref "Q1") (pin "D") (pinfunction "D_D") (pintype "passive"))
      (node (ref "U3") (pin "2") (pinfunction "C_2") (pintype "passive"))
    )
    (net (code "132") (name "Net-(U4-A)") (class "Default")
      (node (ref "R67") (pin "1") (pinfunction "1_1") (pintype "bidirectional"))
      (node (ref "U4") (pin "1") (pinfunction "A_1") (pintype "passive"))
    )
    (net (code "133") (name "Net-(U4-C)") (class "Default")
      (node (ref "Q2") (pin "D") (pinfunction "D_D") (pintype "passive"))
      (node (ref "U4") (pin "2") (pinfunction "C_2") (pintype "passive"))
    )
    (net (code "134") (name "Net-(U6-4:BOOTN)") (class "Default")
      (node (ref "BOOTSEL") (pin "TP") (pinfunction "TP_TP") (pintype "passive"))
      (node (ref "R70") (pin "1") (pinfunction "1_1") (pintype "bidirectional"))
      (node (ref "U6") (pin "4") (pinfunction "4:BOOTN_4") (pintype "input"))
    )
    (net (code "135") (name "Net-(U6-9:CAP)") (class "Default")
      (node (ref "C21") (pin "2") (pinfunction "2_2") (pintype "passive"))
      (node (ref "U6") (pin "9") (pinfunction "9:CAP_9") (pintype "bidirectional"))
    )
    (net (code "136") (name "Net-(U6-10:CLKSEL0)") (class "Default")
      (node (ref "R80") (pin "1") (pinfunction "1_1") (pintype "bidirectional"))
      (node (ref "U6") (pin "10") (pinfunction "10:CLKSEL0_10") (pintype "input"))
    )
    (net (code "137") (name "Net-(U6-11:NRST)") (class "Default")
      (node (ref "R69") (pin "1") (pinfunction "1_1") (pintype "bidirectional"))
      (node (ref "R71") (pin "2") (pinfunction "2_2") (pintype "bidirectional"))
      (node (ref "U6") (pin "11") (pinfunction "11:NRST_11") (pintype "input"))
    )
    (net (code "138") (name "Net-(U6-14:H_INTN)") (class "Default")
      (node (ref "INIT") (pin "TP") (pinfunction "TP_TP") (pintype "passive"))
      (node (ref "U6") (pin "14") (pinfunction "14:H_INTN_14") (pintype "output"))
    )
    (net (code "139") (name "Net-(U6-17:SA0{slash}H_MOSI)") (class "Default")
      (node (ref "R58") (pin "2") (pinfunction "2_2") (pintype "bidirectional"))
      (node (ref "R72") (pin "1") (pinfunction "1_1") (pintype "bidirectional"))
      (node (ref "U6") (pin "17") (pinfunction "17:SA0/H_MOSI_17") (pintype "input"))
    )
    (net (code "140") (name "Net-(U6-26:XOUT32{slash}CLKSEL1)") (class "Default")
      (node (ref "C25") (pin "1") (pinfunction "1_1") (pintype "passive"))
      (node (ref "U6") (pin "26") (pinfunction "26:XOUT32/CLKSEL1_26") (pintype "output"))
      (node (ref "X1") (pin "2") (pinfunction "P$2_2") (pintype "bidirectional"))
    )
    (net (code "141") (name "Net-(U6-27:XIN32)") (class "Default")
      (node (ref "C24") (pin "1") (pinfunction "1_1") (pintype "passive"))
      (node (ref "U6") (pin "27") (pinfunction "27:XIN32_27") (pintype "input"))
      (node (ref "X1") (pin "1") (pinfunction "P$1_1") (pintype "bidirectional"))
    )
    (net (code "142") (name "Net-(U7-BS1)") (class "Default")
      (node (ref "R19") (pin "2") (pinfunction "2_2") (pintype "bidirectional"))
      (node (ref "U7") (pin "20") (pinfunction "BS1_20") (pintype "bidirectional"))
    )
    (net (code "143") (name "Net-(U7-C1N)") (class "Default")
      (node (ref "C19") (pin "1") (pinfunction "1_1") (pintype "passive"))
      (node (ref "U7") (pin "26") (pinfunction "C1N_26") (pintype "bidirectional"))
    )
    (net (code "144") (name "Net-(U7-C1P)") (class "Default")
      (node (ref "C19") (pin "2") (pinfunction "2_2") (pintype "passive"))
      (node (ref "U7") (pin "27") (pinfunction "C1P_27") (pintype "bidirectional"))
    )
    (net (code "145") (name "Net-(U7-C2N)") (class "Default")
      (node (ref "C22") (pin "1") (pinfunction "1_1") (pintype "passive"))
      (node (ref "U7") (pin "28") (pinfunction "C2N_28") (pintype "bidirectional"))
    )
    (net (code "146") (name "Net-(U7-C2P)") (class "Default")
      (node (ref "C22") (pin "2") (pinfunction "2_2") (pintype "passive"))
      (node (ref "U7") (pin "29") (pinfunction "C2P_29") (pintype "bidirectional"))
    )
    (net (code "147") (name "Net-(U7-D{slash}C#)") (class "Default")
      (node (ref "R36") (pin "2") (pinfunction "2_2") (pintype "bidirectional"))
      (node (ref "R37") (pin "1") (pinfunction "1_1") (pintype "bidirectional"))
      (node (ref "U7") (pin "16") (pinfunction "D/C#_16") (pintype "bidirectional"))
    )
    (net (code "148") (name "Net-(U7-IREF)") (class "Default")
      (node (ref "R13") (pin "1") (pinfunction "1_1") (pintype "bidirectional"))
      (node (ref "U7") (pin "5") (pinfunction "IREF_5") (pintype "bidirectional"))
    )
    (net (code "149") (name "Net-(U7-VCC)") (class "Default")
      (node (ref "C13") (pin "2") (pinfunction "2_2") (pintype "passive"))
      (node (ref "U7") (pin "3") (pinfunction "VCC_3") (pintype "bidirectional"))
    )
    (net (code "150") (name "Net-(U7-VCOMH)") (class "Default")
      (node (ref "C16") (pin "2") (pinfunction "2_2") (pintype "passive"))
      (node (ref "U7") (pin "4") (pinfunction "VCOMH_4") (pintype "bidirectional"))
    )
    (net (code "151") (name "VSPI") (class "Default")
      (node (ref "R76") (pin "1") (pinfunction "1_1") (pintype "bidirectional"))
      (node (ref "R77") (pin "1") (pinfunction "1_1") (pintype "bidirectional"))
      (node (ref "R78") (pin "1") (pinfunction "1_1") (pintype "bidirectional"))
      (node (ref "R79") (pin "1") (pinfunction "1_1") (pintype "bidirectional"))
      (node (ref "U$14") (pin "15:GPIO45") (pinfunction "15:GPIO45/VSPI_15:GPIO45") (pintype "power_in"))
      (node (ref "U$14") (pin "15:GPIO45_R") (pinfunction "15:GPIO45/VSPI_15:GPIO45_R") (pintype "power_in"))
    )
    (net (code "152") (name "unconnected-(GPIO40-CE1-Pad26)") (class "Default")
      (node (ref "GPIO40") (pin "26") (pinfunction "CE1_26") (pintype "bidirectional"))
    )
    (net (code "153") (name "unconnected-(GPIO40-ID_SC-Pad28)") (class "Default")
      (node (ref "GPIO40") (pin "28") (pinfunction "ID_SC_28") (pintype "bidirectional"))
    )
    (net (code "154") (name "unconnected-(GPIO40-ID_SD-Pad27)") (class "Default")
      (node (ref "GPIO40") (pin "27") (pinfunction "ID_SD_27") (pintype "bidirectional"))
    )
    (net (code "155") (name "unconnected-(IC2-LED2-Pad8)") (class "Default")
      (node (ref "IC2") (pin "8") (pinfunction "LED2_8") (pintype "bidirectional"))
    )
    (net (code "156") (name "unconnected-(IC2-LED3-Pad9)") (class "Default")
      (node (ref "IC2") (pin "9") (pinfunction "LED3_9") (pintype "bidirectional"))
    )
    (net (code "157") (name "unconnected-(IC2-LED4-Pad10)") (class "Default")
      (node (ref "IC2") (pin "10") (pinfunction "LED4_10") (pintype "bidirectional"))
    )
    (net (code "158") (name "unconnected-(IC2-LED5-Pad11)") (class "Default")
      (node (ref "IC2") (pin "11") (pinfunction "LED5_11") (pintype "bidirectional"))
    )
    (net (code "159") (name "unconnected-(IC2-LED6-Pad12)") (class "Default")
      (node (ref "IC2") (pin "12") (pinfunction "LED6_12") (pintype "bidirectional"))
    )
    (net (code "160") (name "unconnected-(IC2-LED7-Pad13)") (class "Default")
      (node (ref "IC2") (pin "13") (pinfunction "LED7_13") (pintype "bidirectional"))
    )
    (net (code "161") (name "unconnected-(IC2-LED8-Pad15)") (class "Default")
      (node (ref "IC2") (pin "15") (pinfunction "LED8_15") (pintype "bidirectional"))
    )
    (net (code "162") (name "unconnected-(IC2-LED9-Pad16)") (class "Default")
      (node (ref "IC2") (pin "16") (pinfunction "LED9_16") (pintype "bidirectional"))
    )
    (net (code "163") (name "unconnected-(IC2-LED10-Pad17)") (class "Default")
      (node (ref "IC2") (pin "17") (pinfunction "LED10_17") (pintype "bidirectional"))
    )
    (net (code "164") (name "unconnected-(IC2-LED11-Pad18)") (class "Default")
      (node (ref "IC2") (pin "18") (pinfunction "LED11_18") (pintype "bidirectional"))
    )
    (net (code "165") (name "unconnected-(IC2-LED12-Pad19)") (class "Default")
      (node (ref "IC2") (pin "19") (pinfunction "LED12_19") (pintype "bidirectional"))
    )
    (net (code "166") (name "unconnected-(IC2-LED13-Pad20)") (class "Default")
      (node (ref "IC2") (pin "20") (pinfunction "LED13_20") (pintype "bidirectional"))
    )
    (net (code "167") (name "unconnected-(IC2-LED15-Pad22)") (class "Default")
      (node (ref "IC2") (pin "22") (pinfunction "LED15_22") (pintype "bidirectional"))
    )
    (net (code "168") (name "unconnected-(U$1-9:Y2-Pad9)") (class "Default")
      (node (ref "U$1") (pin "9") (pinfunction "9:Y2_9") (pintype "bidirectional"))
    )
    (net (code "169") (name "unconnected-(U$1-12:Y3-Pad12)") (class "Default")
      (node (ref "U$1") (pin "12") (pinfunction "12:Y3_12") (pintype "bidirectional"))
    )
    (net (code "170") (name "unconnected-(U$5-2:3Y-Pad2)") (class "Default")
      (node (ref "U$5") (pin "2") (pinfunction "2:3Y_2") (pintype "open_collector"))
    )
    (net (code "171") (name "unconnected-(U6-1:RESV_NC-Pad1)") (class "Default")
      (node (ref "U6") (pin "1") (pinfunction "1:RESV_NC_1") (pintype "no_connect"))
    )
    (net (code "172") (name "unconnected-(U6-7:RESV_NC-Pad7)") (class "Default")
      (node (ref "U6") (pin "7") (pinfunction "7:RESV_NC_7") (pintype "no_connect"))
    )
    (net (code "173") (name "unconnected-(U6-8:RESV_NC-Pad8)") (class "Default")
      (node (ref "U6") (pin "8") (pinfunction "8:RESV_NC_8") (pintype "no_connect"))
    )
    (net (code "174") (name "unconnected-(U6-12:RESV_NC-Pad12)") (class "Default")
      (node (ref "U6") (pin "12") (pinfunction "12:RESV_NC_12") (pintype "no_connect"))
    )
    (net (code "175") (name "unconnected-(U6-13:RESV_NC-Pad13)") (class "Default")
      (node (ref "U6") (pin "13") (pinfunction "13:RESV_NC_13") (pintype "no_connect"))
    )
    (net (code "176") (name "unconnected-(U6-15:ENV_SCL-Pad15)") (class "Default")
      (node (ref "U6") (pin "15") (pinfunction "15:ENV_SCL_15") (pintype "bidirectional"))
    )
    (net (code "177") (name "unconnected-(U6-16:ENV_SDA-Pad16)") (class "Default")
      (node (ref "U6") (pin "16") (pinfunction "16:ENV_SDA_16") (pintype "bidirectional"))
    )
    (net (code "178") (name "unconnected-(U6-21:RESV_NC-Pad21)") (class "Default")
      (node (ref "U6") (pin "21") (pinfunction "21:RESV_NC_21") (pintype "no_connect"))
    )
    (net (code "179") (name "unconnected-(U6-22:RESV_NC-Pad22)") (class "Default")
      (node (ref "U6") (pin "22") (pinfunction "22:RESV_NC_22") (pintype "no_connect"))
    )
    (net (code "180") (name "unconnected-(U6-23:RESV_NC-Pad23)") (class "Default")
      (node (ref "U6") (pin "23") (pinfunction "23:RESV_NC_23") (pintype "no_connect"))
    )
    (net (code "181") (name "unconnected-(U6-24:RESV_NC-Pad24)") (class "Default")
      (node (ref "U6") (pin "24") (pinfunction "24:RESV_NC_24") (pintype "no_connect"))
    )
    (net (code "182") (name "unconnected-(U7-NC-Pad1)") (class "Default")
      (node (ref "U7") (pin "1") (pinfunction "NC_1") (pintype "bidirectional"))
    )
    (net (code "183") (name "unconnected-(U7-NC-Pad24)") (class "Default")
      (node (ref "U7") (pin "24") (pinfunction "NC_24") (pintype "bidirectional"))
    )
    (net (code "184") (name "unconnected-(U7-NC-Pad30)") (class "Default")
      (node (ref "U7") (pin "30") (pinfunction "NC_30") (pintype "bidirectional"))
    )
  )
)
